# StaticPlatformMain_v1.net
KiCad netlist of a schematic drawn in EAGLE
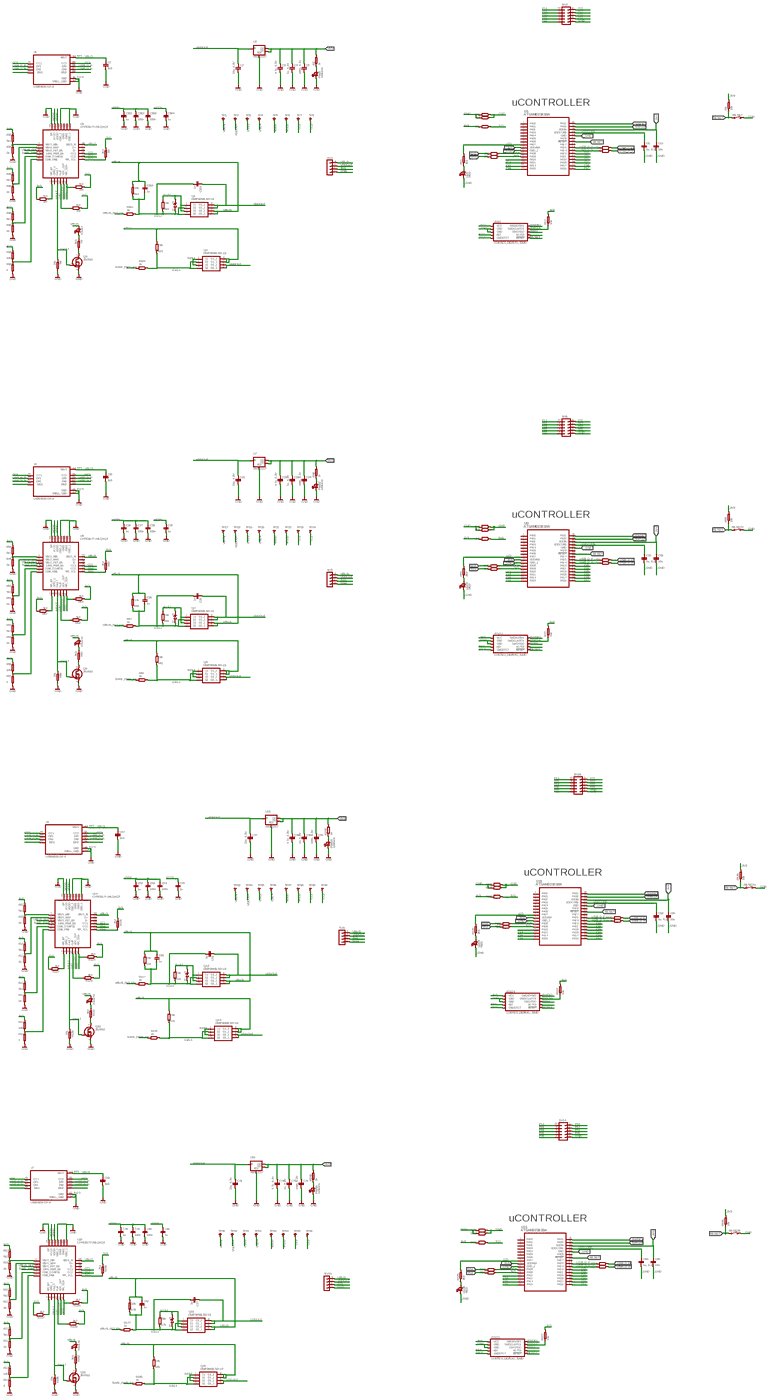
[diagram p0: schematic, sheet 1, overview]
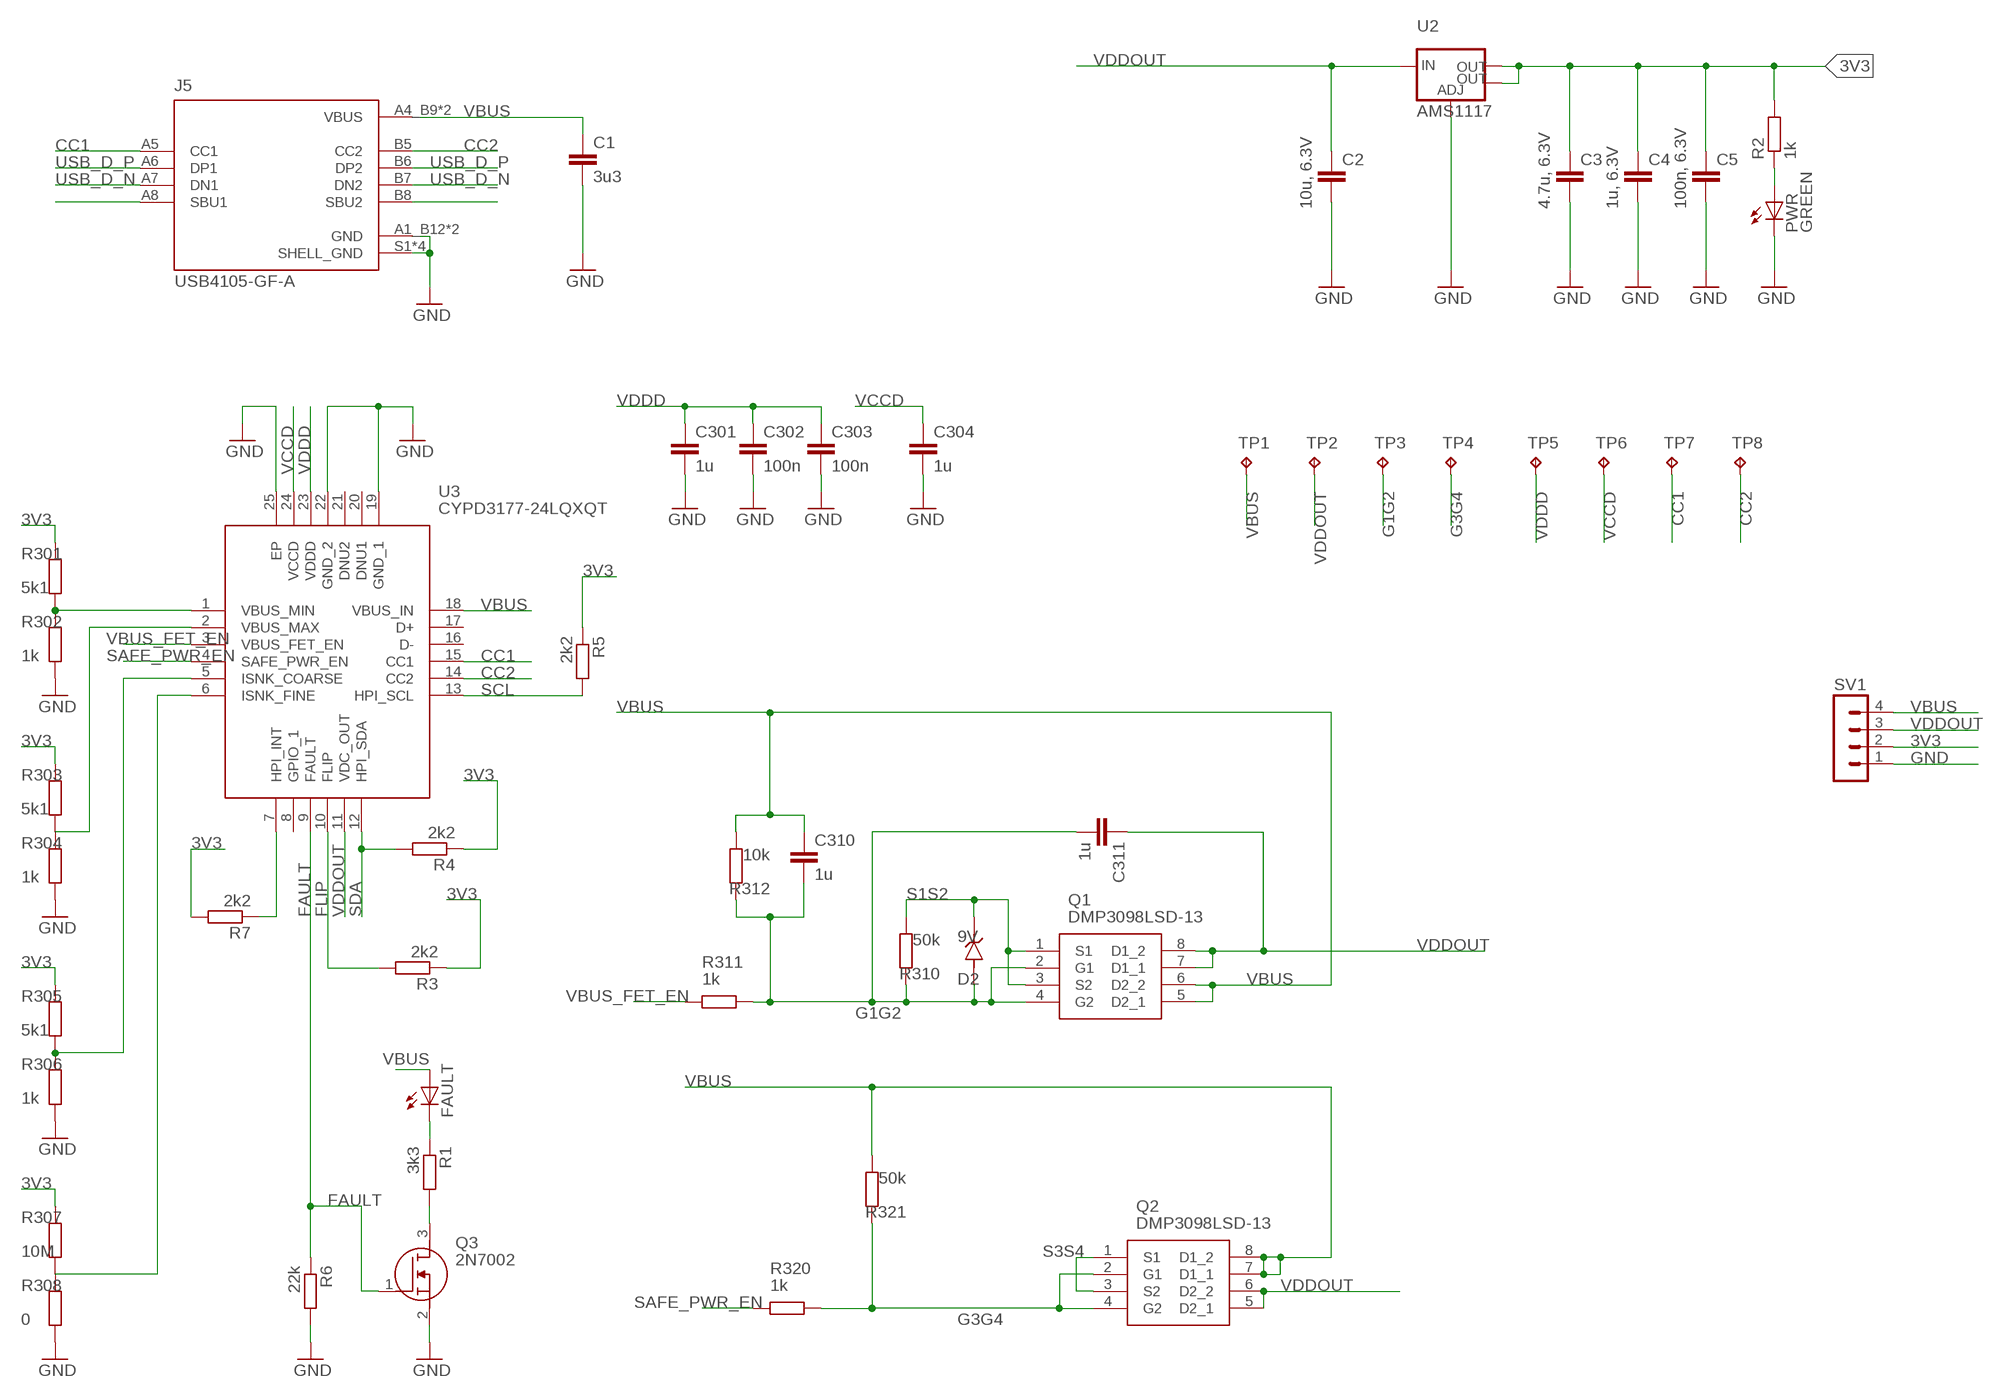
[diagram p1: schematic, sheet 1, part 1 of 6]
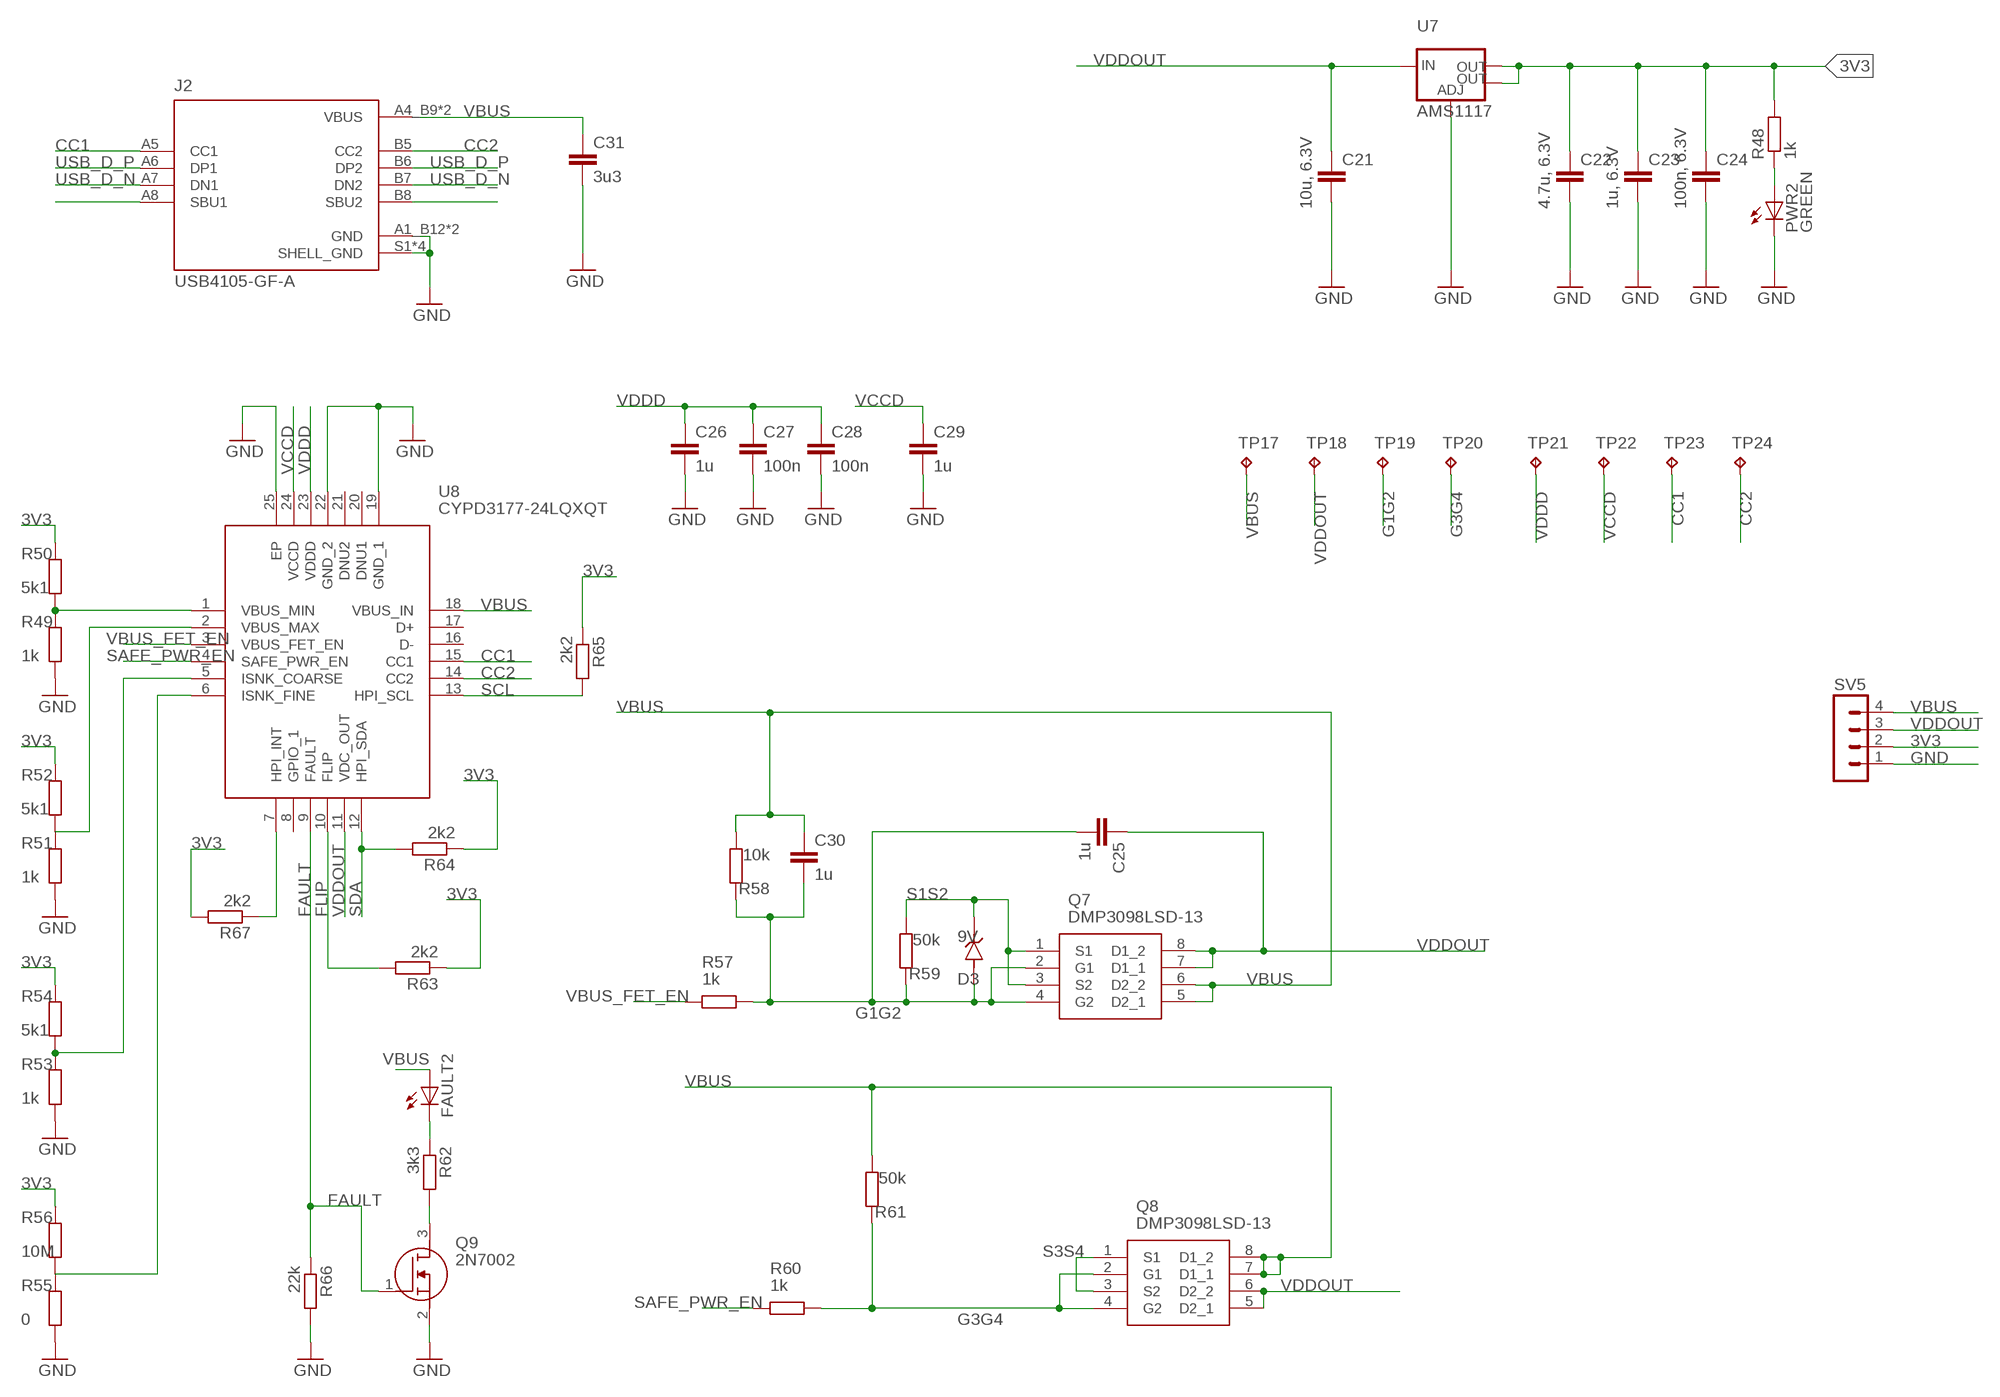
[diagram p2: schematic, sheet 1, part 2 of 6]
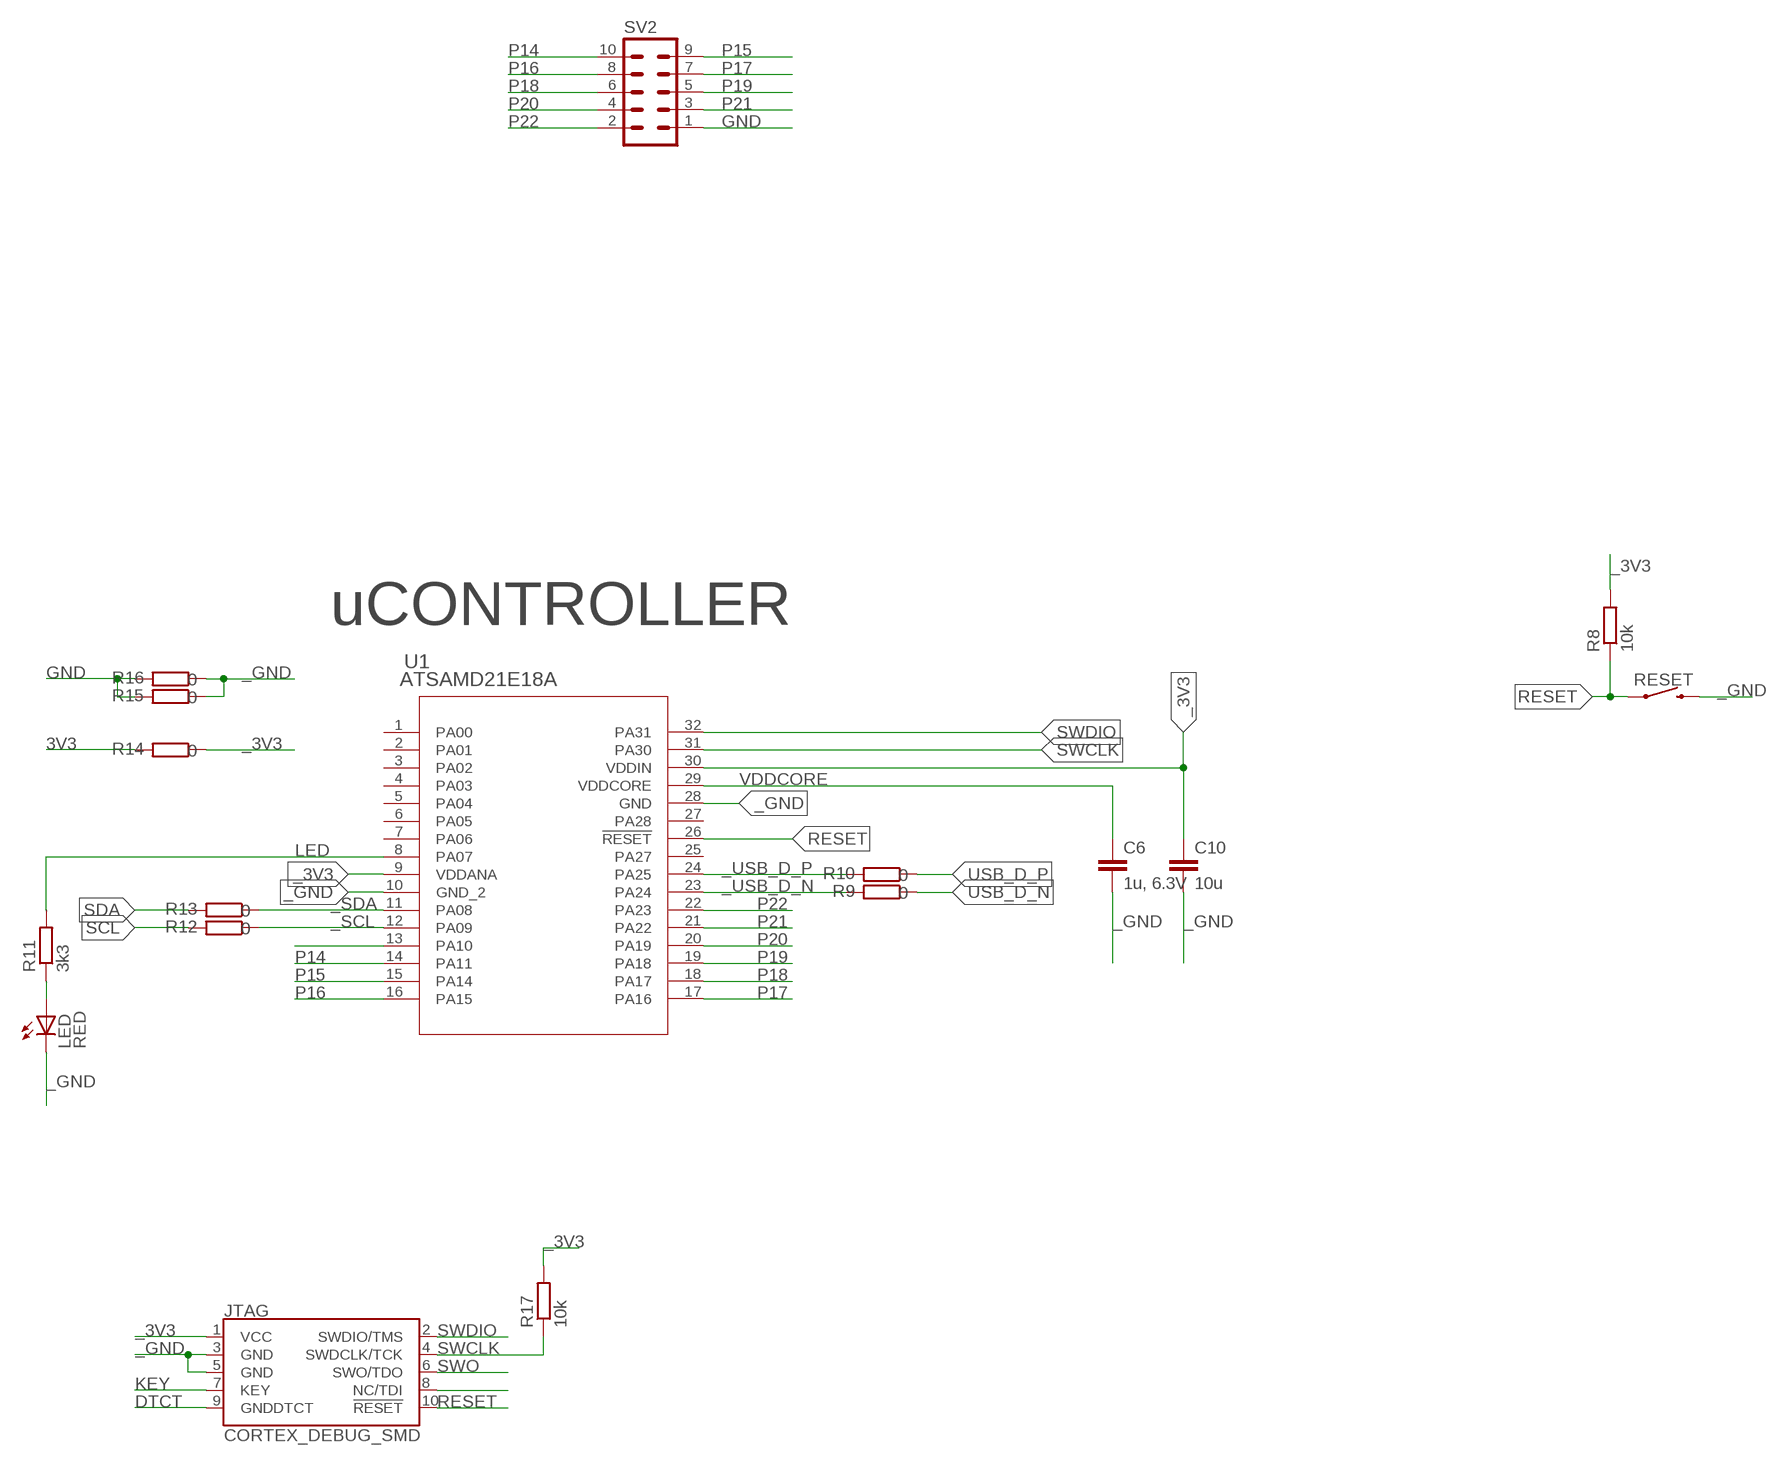
[diagram p3: schematic, sheet 1, part 3 of 6]
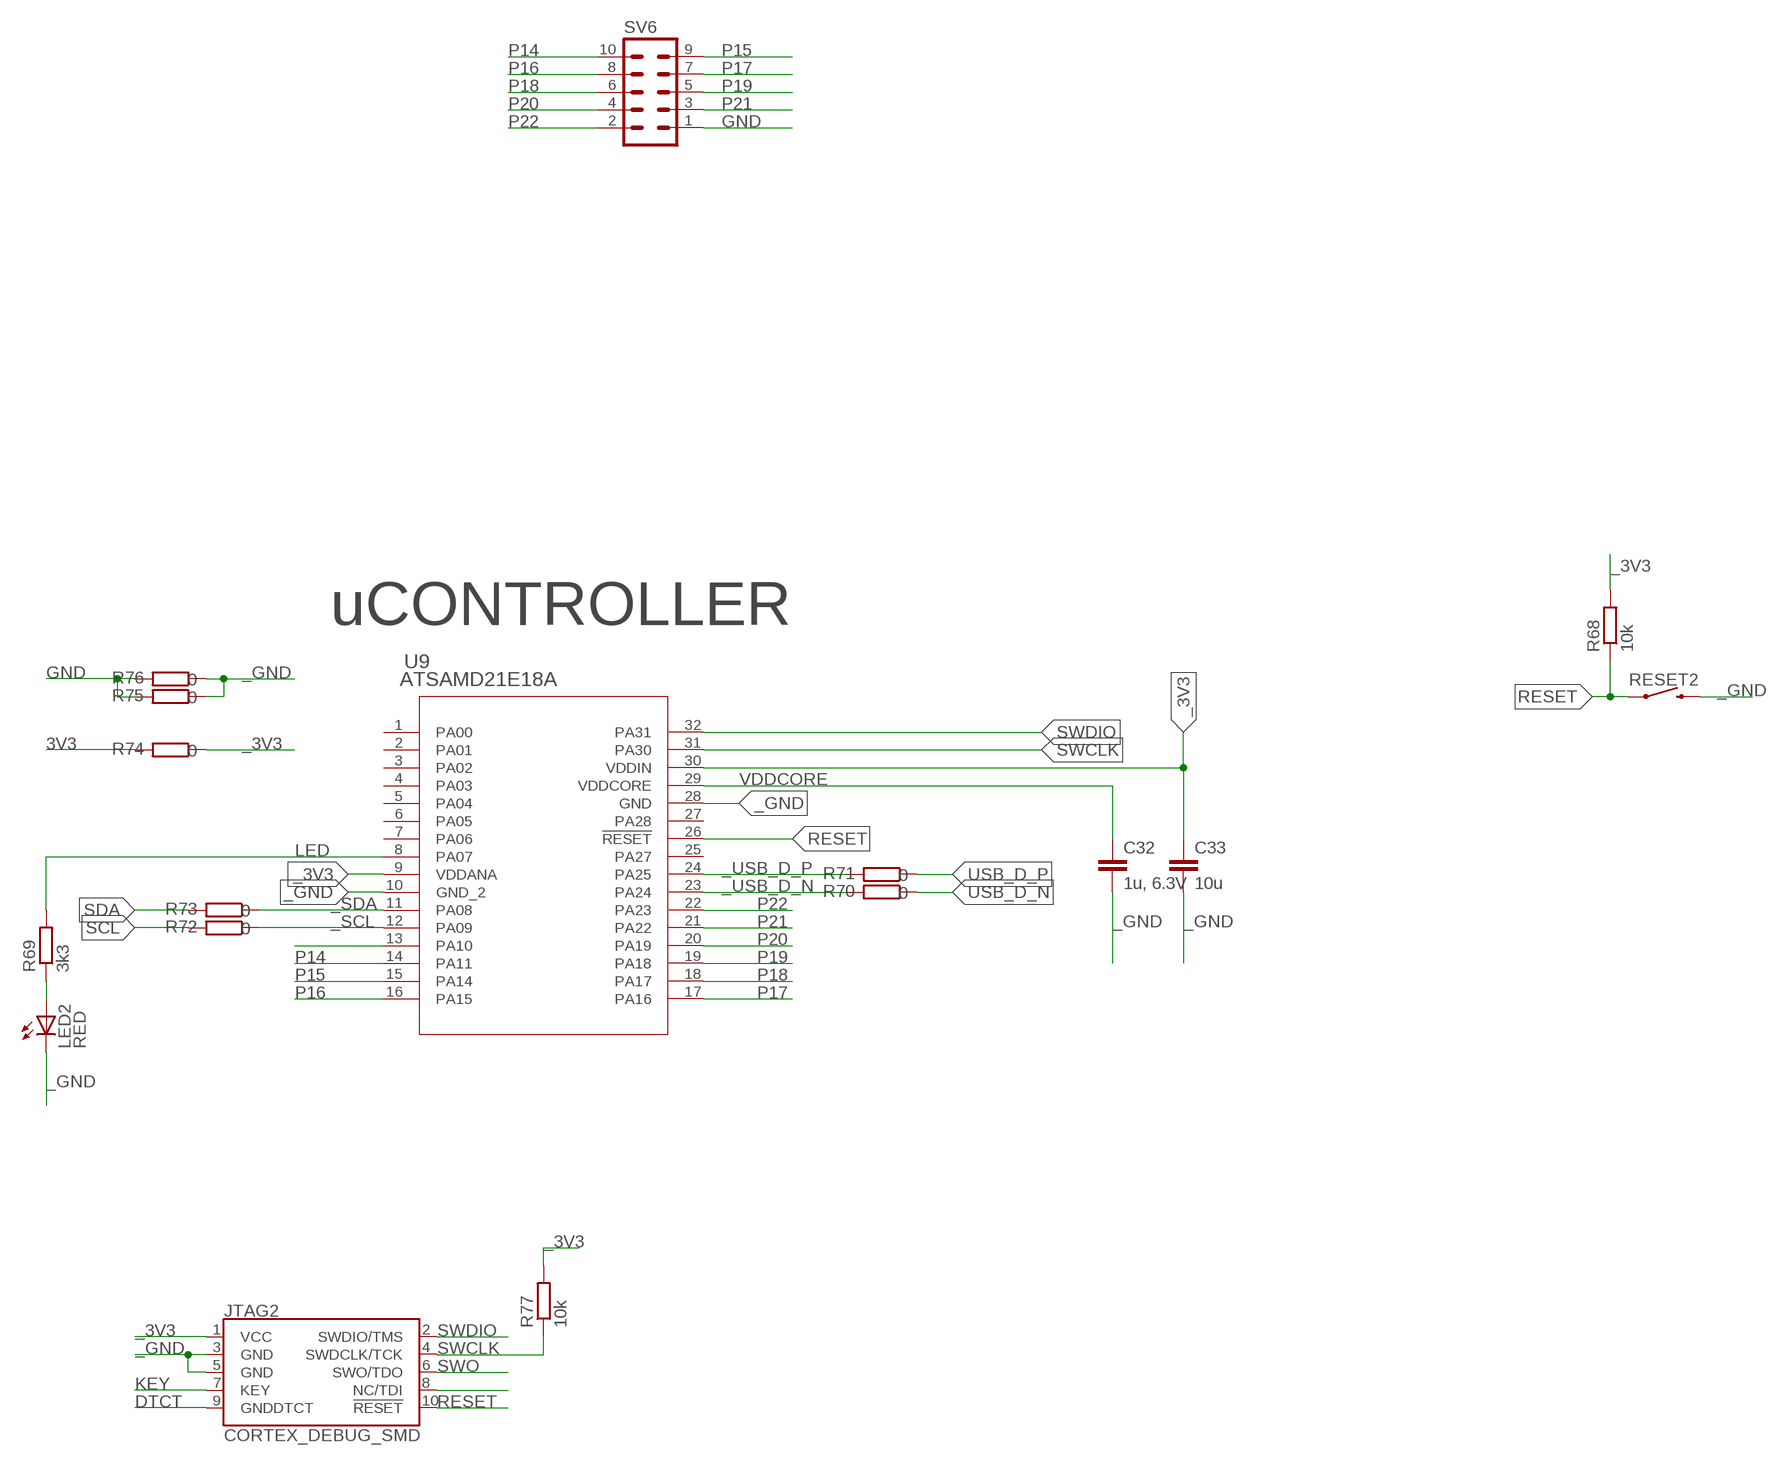
[diagram p4: schematic, sheet 1, part 4 of 6]
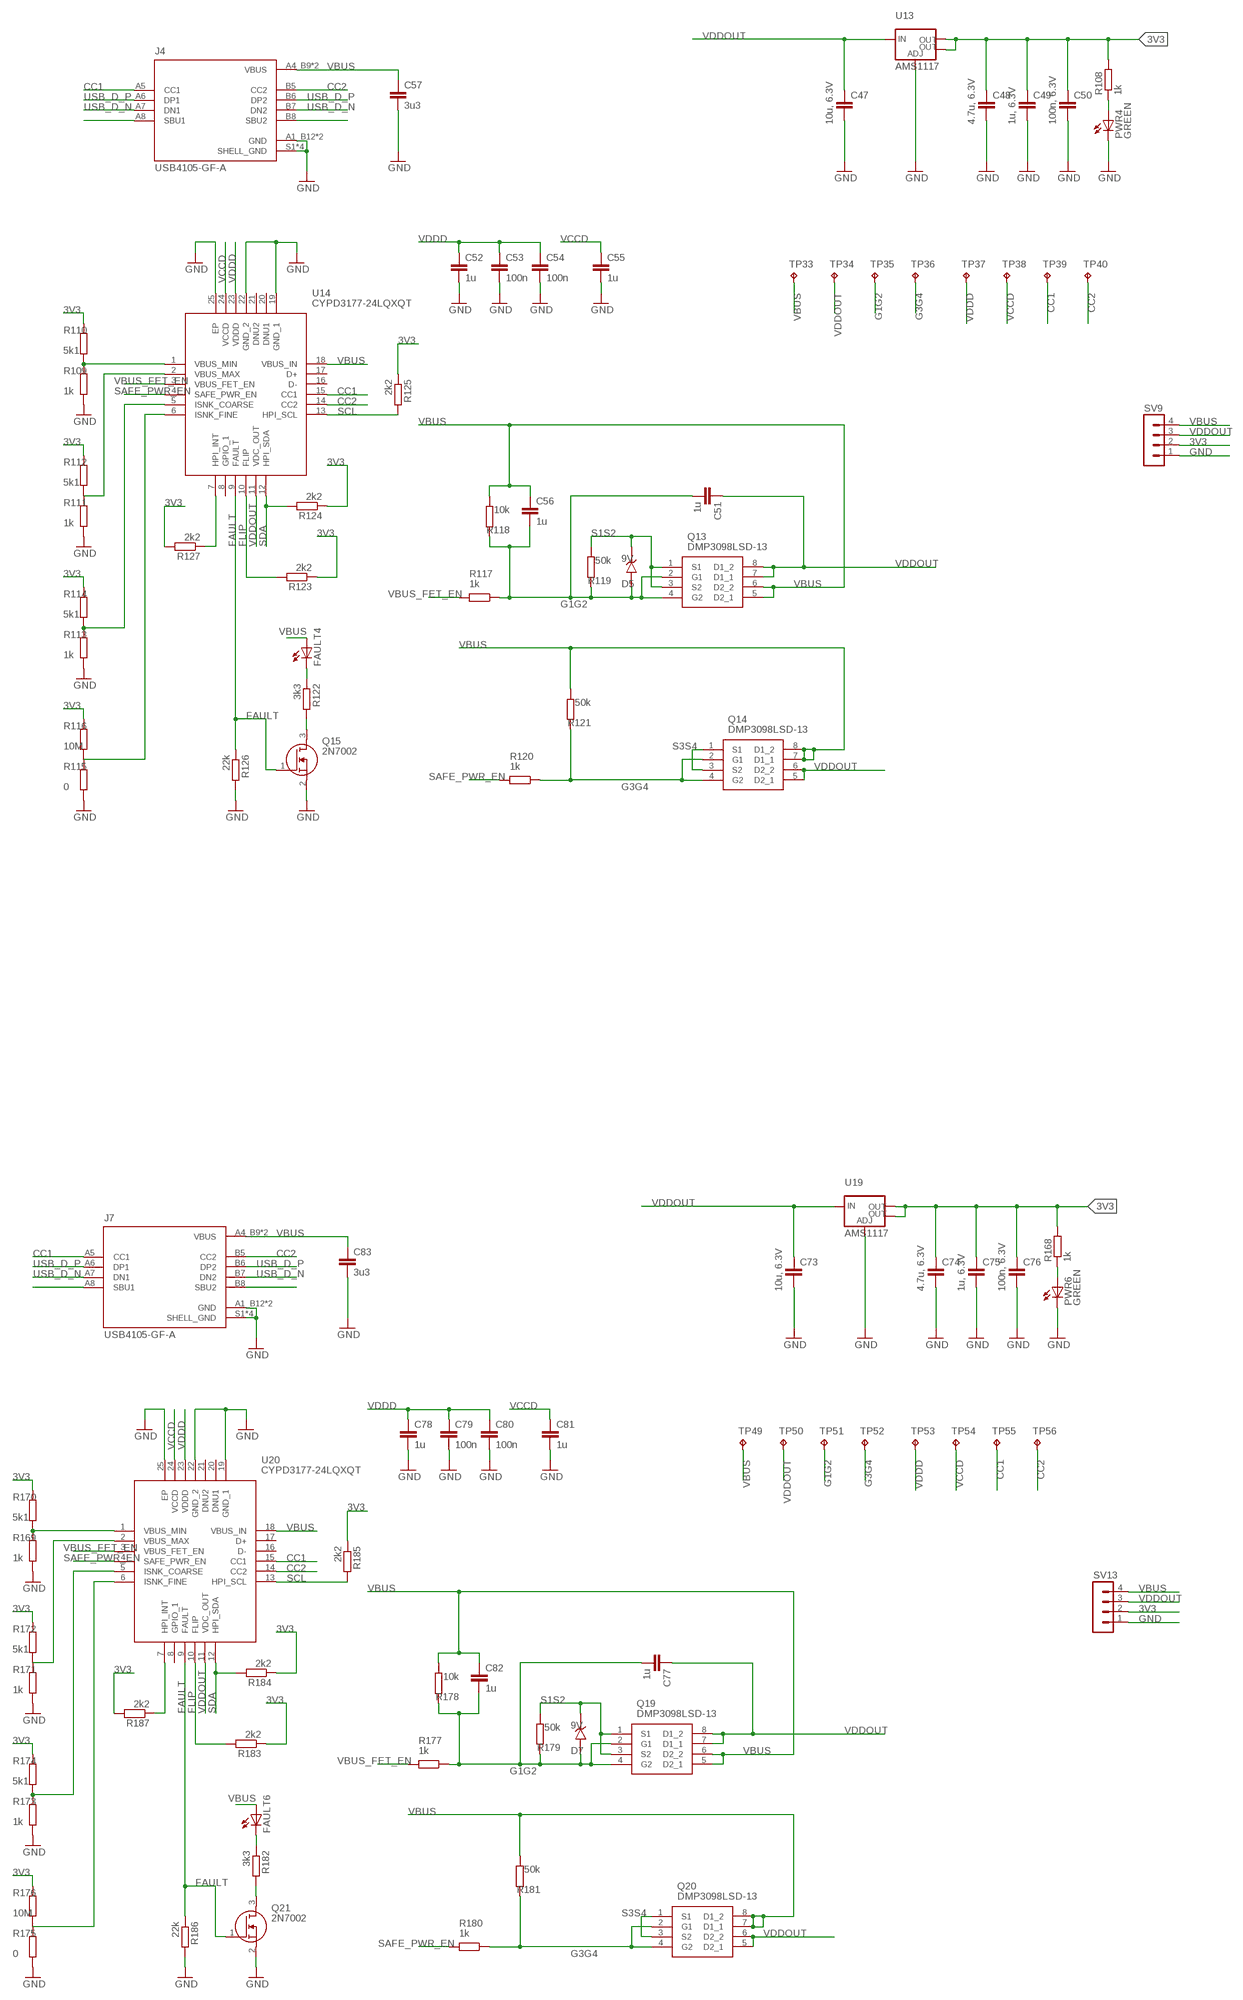
[diagram p5: schematic, sheet 1, part 5 of 6]
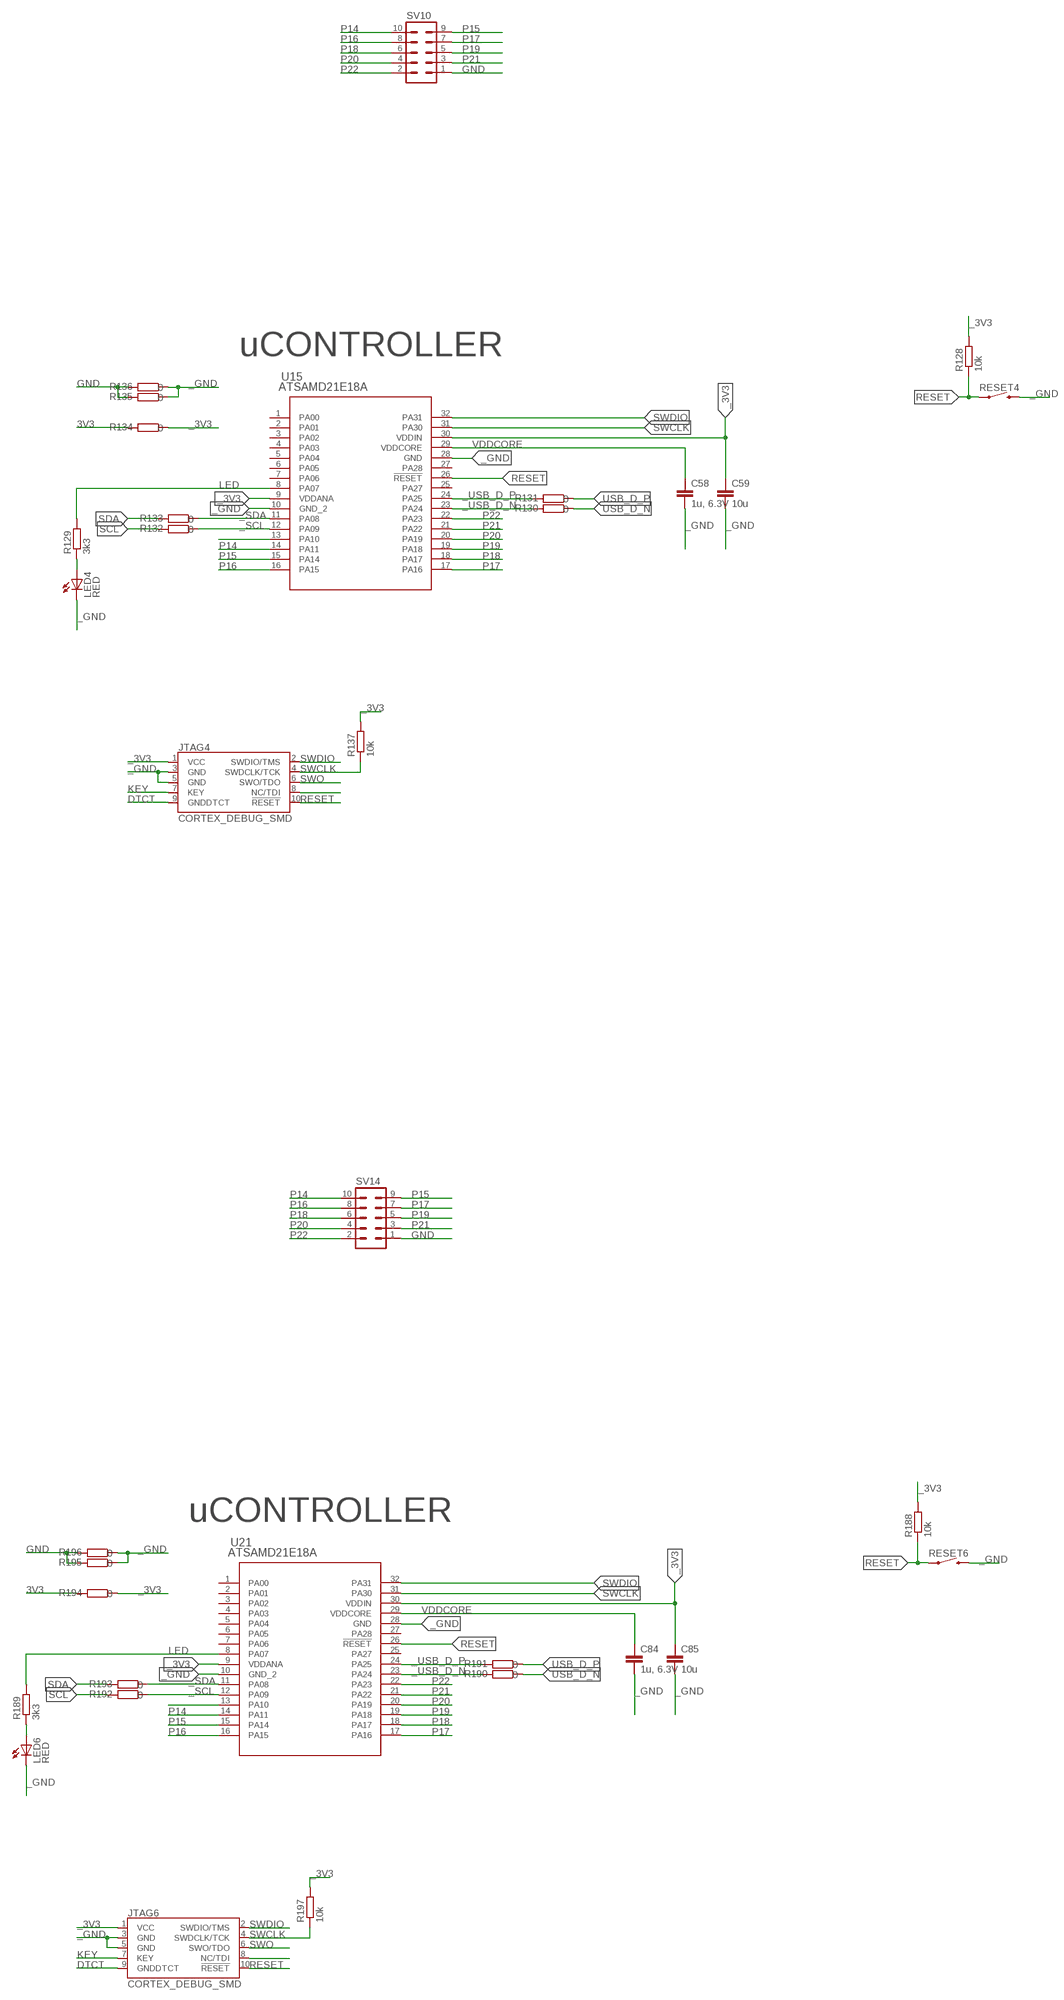
[diagram p6: schematic, sheet 1, part 6 of 6]

(export (version "E")
  (design (tool "Eeschema 10.0.6"))
  (components
    (comp (ref "C1")
      (value "3u3")
      (footprint "eagle-import:C0805K")
      (libsource (lib "eagle-import") (part "C-EUC0805K"))
    )
    (comp (ref "C2")
      (value "10u, 6.3V")
      (footprint "eagle-import:C0805K")
      (libsource (lib "eagle-import") (part "C-EUC0805K"))
    )
    (comp (ref "C3")
      (value "4.7u, 6.3V")
      (footprint "eagle-import:C0805K")
      (libsource (lib "eagle-import") (part "C-EUC0805K"))
    )
    (comp (ref "C4")
      (value "1u, 6.3V")
      (footprint "eagle-import:C0805K")
      (libsource (lib "eagle-import") (part "C-EUC0805K"))
    )
    (comp (ref "C5")
      (value "100n, 6.3V")
      (footprint "eagle-import:C0805K")
      (libsource (lib "eagle-import") (part "C-EUC0805K"))
    )
    (comp (ref "C6")
      (value "1u, 6.3V")
      (footprint "eagle-import:C0805")
      (libsource (lib "eagle-import") (part "C-EUC0805"))
    )
    (comp (ref "C10")
      (value "10u")
      (footprint "eagle-import:C0805")
      (libsource (lib "eagle-import") (part "C-EUC0805"))
    )
    (comp (ref "C21")
      (value "10u, 6.3V")
      (footprint "eagle-import:C0805K")
      (libsource (lib "eagle-import") (part "C-EUC0805K"))
    )
    (comp (ref "C22")
      (value "4.7u, 6.3V")
      (footprint "eagle-import:C0805K")
      (libsource (lib "eagle-import") (part "C-EUC0805K"))
    )
    (comp (ref "C23")
      (value "1u, 6.3V")
      (footprint "eagle-import:C0805K")
      (libsource (lib "eagle-import") (part "C-EUC0805K"))
    )
    (comp (ref "C24")
      (value "100n, 6.3V")
      (footprint "eagle-import:C0805K")
      (libsource (lib "eagle-import") (part "C-EUC0805K"))
    )
    (comp (ref "C25")
      (value "1u")
      (footprint "eagle-import:C0805K")
      (libsource (lib "eagle-import") (part "C-EUC0805K"))
    )
    (comp (ref "C26")
      (value "1u")
      (footprint "eagle-import:C0805K")
      (libsource (lib "eagle-import") (part "C-EUC0805K"))
    )
    (comp (ref "C27")
      (value "100n")
      (footprint "eagle-import:C0805K")
      (libsource (lib "eagle-import") (part "C-EUC0805K"))
    )
    (comp (ref "C28")
      (value "100n")
      (footprint "eagle-import:C0805K")
      (libsource (lib "eagle-import") (part "C-EUC0805K"))
    )
    (comp (ref "C29")
      (value "1u")
      (footprint "eagle-import:C0805K")
      (libsource (lib "eagle-import") (part "C-EUC0805K"))
    )
    (comp (ref "C30")
      (value "1u")
      (footprint "eagle-import:C0805K")
      (libsource (lib "eagle-import") (part "C-EUC0805K"))
    )
    (comp (ref "C31")
      (value "3u3")
      (footprint "eagle-import:C0805K")
      (libsource (lib "eagle-import") (part "C-EUC0805K"))
    )
    (comp (ref "C32")
      (value "1u, 6.3V")
      (footprint "eagle-import:C0805")
      (libsource (lib "eagle-import") (part "C-EUC0805"))
    )
    (comp (ref "C33")
      (value "10u")
      (footprint "eagle-import:C0805")
      (libsource (lib "eagle-import") (part "C-EUC0805"))
    )
    (comp (ref "C47")
      (value "10u, 6.3V")
      (footprint "eagle-import:C0805K")
      (libsource (lib "eagle-import") (part "C-EUC0805K"))
    )
    (comp (ref "C48")
      (value "4.7u, 6.3V")
      (footprint "eagle-import:C0805K")
      (libsource (lib "eagle-import") (part "C-EUC0805K"))
    )
    (comp (ref "C49")
      (value "1u, 6.3V")
      (footprint "eagle-import:C0805K")
      (libsource (lib "eagle-import") (part "C-EUC0805K"))
    )
    (comp (ref "C50")
      (value "100n, 6.3V")
      (footprint "eagle-import:C0805K")
      (libsource (lib "eagle-import") (part "C-EUC0805K"))
    )
    (comp (ref "C51")
      (value "1u")
      (footprint "eagle-import:C0805K")
      (libsource (lib "eagle-import") (part "C-EUC0805K"))
    )
    (comp (ref "C52")
      (value "1u")
      (footprint "eagle-import:C0805K")
      (libsource (lib "eagle-import") (part "C-EUC0805K"))
    )
    (comp (ref "C53")
      (value "100n")
      (footprint "eagle-import:C0805K")
      (libsource (lib "eagle-import") (part "C-EUC0805K"))
    )
    (comp (ref "C54")
      (value "100n")
      (footprint "eagle-import:C0805K")
      (libsource (lib "eagle-import") (part "C-EUC0805K"))
    )
    (comp (ref "C55")
      (value "1u")
      (footprint "eagle-import:C0805K")
      (libsource (lib "eagle-import") (part "C-EUC0805K"))
    )
    (comp (ref "C56")
      (value "1u")
      (footprint "eagle-import:C0805K")
      (libsource (lib "eagle-import") (part "C-EUC0805K"))
    )
    (comp (ref "C57")
      (value "3u3")
      (footprint "eagle-import:C0805K")
      (libsource (lib "eagle-import") (part "C-EUC0805K"))
    )
    (comp (ref "C58")
      (value "1u, 6.3V")
      (footprint "eagle-import:C0805")
      (libsource (lib "eagle-import") (part "C-EUC0805"))
    )
    (comp (ref "C59")
      (value "10u")
      (footprint "eagle-import:C0805")
      (libsource (lib "eagle-import") (part "C-EUC0805"))
    )
    (comp (ref "C73")
      (value "10u, 6.3V")
      (footprint "eagle-import:C0805K")
      (libsource (lib "eagle-import") (part "C-EUC0805K"))
    )
    (comp (ref "C74")
      (value "4.7u, 6.3V")
      (footprint "eagle-import:C0805K")
      (libsource (lib "eagle-import") (part "C-EUC0805K"))
    )
    (comp (ref "C75")
      (value "1u, 6.3V")
      (footprint "eagle-import:C0805K")
      (libsource (lib "eagle-import") (part "C-EUC0805K"))
    )
    (comp (ref "C76")
      (value "100n, 6.3V")
      (footprint "eagle-import:C0805K")
      (libsource (lib "eagle-import") (part "C-EUC0805K"))
    )
    (comp (ref "C77")
      (value "1u")
      (footprint "eagle-import:C0805K")
      (libsource (lib "eagle-import") (part "C-EUC0805K"))
    )
    (comp (ref "C78")
      (value "1u")
      (footprint "eagle-import:C0805K")
      (libsource (lib "eagle-import") (part "C-EUC0805K"))
    )
    (comp (ref "C79")
      (value "100n")
      (footprint "eagle-import:C0805K")
      (libsource (lib "eagle-import") (part "C-EUC0805K"))
    )
    (comp (ref "C80")
      (value "100n")
      (footprint "eagle-import:C0805K")
      (libsource (lib "eagle-import") (part "C-EUC0805K"))
    )
    (comp (ref "C81")
      (value "1u")
      (footprint "eagle-import:C0805K")
      (libsource (lib "eagle-import") (part "C-EUC0805K"))
    )
    (comp (ref "C82")
      (value "1u")
      (footprint "eagle-import:C0805K")
      (libsource (lib "eagle-import") (part "C-EUC0805K"))
    )
    (comp (ref "C83")
      (value "3u3")
      (footprint "eagle-import:C0805K")
      (libsource (lib "eagle-import") (part "C-EUC0805K"))
    )
    (comp (ref "C84")
      (value "1u, 6.3V")
      (footprint "eagle-import:C0805")
      (libsource (lib "eagle-import") (part "C-EUC0805"))
    )
    (comp (ref "C85")
      (value "10u")
      (footprint "eagle-import:C0805")
      (libsource (lib "eagle-import") (part "C-EUC0805"))
    )
    (comp (ref "C301")
      (value "1u")
      (footprint "eagle-import:C0805K")
      (libsource (lib "eagle-import") (part "C-EUC0805K"))
    )
    (comp (ref "C302")
      (value "100n")
      (footprint "eagle-import:C0805K")
      (libsource (lib "eagle-import") (part "C-EUC0805K"))
    )
    (comp (ref "C303")
      (value "100n")
      (footprint "eagle-import:C0805K")
      (libsource (lib "eagle-import") (part "C-EUC0805K"))
    )
    (comp (ref "C304")
      (value "1u")
      (footprint "eagle-import:C0805K")
      (libsource (lib "eagle-import") (part "C-EUC0805K"))
    )
    (comp (ref "C310")
      (value "1u")
      (footprint "eagle-import:C0805K")
      (libsource (lib "eagle-import") (part "C-EUC0805K"))
    )
    (comp (ref "C311")
      (value "1u")
      (footprint "eagle-import:C0805K")
      (libsource (lib "eagle-import") (part "C-EUC0805K"))
    )
    (comp (ref "D2")
      (value "9V")
      (footprint "eagle-import:DIOMELF3515N")
      (fields (field (name "MF") "Taiwan Semiconductor Corporation") (field (name "MP") "BZV55C12 L0G"))
      (libsource (lib "eagle-import") (part "BZV55C12_L0G"))
    )
    (comp (ref "D3")
      (value "9V")
      (footprint "eagle-import:DIOMELF3515N")
      (fields (field (name "MF") "Taiwan Semiconductor Corporation") (field (name "MP") "BZV55C12 L0G"))
      (libsource (lib "eagle-import") (part "BZV55C12_L0G"))
    )
    (comp (ref "D5")
      (value "9V")
      (footprint "eagle-import:DIOMELF3515N")
      (fields (field (name "MF") "Taiwan Semiconductor Corporation") (field (name "MP") "BZV55C12 L0G"))
      (libsource (lib "eagle-import") (part "BZV55C12_L0G"))
    )
    (comp (ref "D7")
      (value "9V")
      (footprint "eagle-import:DIOMELF3515N")
      (fields (field (name "MF") "Taiwan Semiconductor Corporation") (field (name "MP") "BZV55C12 L0G"))
      (libsource (lib "eagle-import") (part "BZV55C12_L0G"))
    )
    (comp (ref "FAULT")
      (value "GREEN")
      (footprint "eagle-import:CHIPLED_0805")
      (libsource (lib "eagle-import") (part "LEDCHIPLED_0805"))
    )
    (comp (ref "FAULT2")
      (value "GREEN")
      (footprint "eagle-import:CHIPLED_0805")
      (libsource (lib "eagle-import") (part "LEDCHIPLED_0805"))
    )
    (comp (ref "FAULT4")
      (value "GREEN")
      (footprint "eagle-import:CHIPLED_0805")
      (libsource (lib "eagle-import") (part "LEDCHIPLED_0805"))
    )
    (comp (ref "FAULT6")
      (value "GREEN")
      (footprint "eagle-import:CHIPLED_0805")
      (libsource (lib "eagle-import") (part "LEDCHIPLED_0805"))
    )
    (comp (ref "J2")
      (value "USB4105-GF-A")
      (footprint "eagle-import:GCT_USB4105-GF-A")
      (fields (field (name "MF") "GCT"))
      (libsource (lib "eagle-import") (part "USB4105-GF-A"))
    )
    (comp (ref "J4")
      (value "USB4105-GF-A")
      (footprint "eagle-import:GCT_USB4105-GF-A")
      (fields (field (name "MF") "GCT"))
      (libsource (lib "eagle-import") (part "USB4105-GF-A"))
    )
    (comp (ref "J5")
      (value "USB4105-GF-A")
      (footprint "eagle-import:GCT_USB4105-GF-A")
      (fields (field (name "MF") "GCT"))
      (libsource (lib "eagle-import") (part "USB4105-GF-A"))
    )
    (comp (ref "J7")
      (value "USB4105-GF-A")
      (footprint "eagle-import:GCT_USB4105-GF-A")
      (fields (field (name "MF") "GCT"))
      (libsource (lib "eagle-import") (part "USB4105-GF-A"))
    )
    (comp (ref "JTAG")
      (value "CORTEX_DEBUG_SMD")
      (footprint "eagle-import:SAMTECH_FTSH-105-01")
      (libsource (lib "eagle-import") (part "CORTEX_DEBUG_SMD"))
    )
    (comp (ref "JTAG2")
      (value "CORTEX_DEBUG_SMD")
      (footprint "eagle-import:SAMTECH_FTSH-105-01")
      (libsource (lib "eagle-import") (part "CORTEX_DEBUG_SMD"))
    )
    (comp (ref "JTAG4")
      (value "CORTEX_DEBUG_SMD")
      (footprint "eagle-import:SAMTECH_FTSH-105-01")
      (libsource (lib "eagle-import") (part "CORTEX_DEBUG_SMD"))
    )
    (comp (ref "JTAG6")
      (value "CORTEX_DEBUG_SMD")
      (footprint "eagle-import:SAMTECH_FTSH-105-01")
      (libsource (lib "eagle-import") (part "CORTEX_DEBUG_SMD"))
    )
    (comp (ref "LED")
      (value "RED")
      (footprint "eagle-import:CHIPLED_0805")
      (libsource (lib "eagle-import") (part "LEDCHIPLED_0805"))
    )
    (comp (ref "LED2")
      (value "RED")
      (footprint "eagle-import:CHIPLED_0805")
      (libsource (lib "eagle-import") (part "LEDCHIPLED_0805"))
    )
    (comp (ref "LED4")
      (value "RED")
      (footprint "eagle-import:CHIPLED_0805")
      (libsource (lib "eagle-import") (part "LEDCHIPLED_0805"))
    )
    (comp (ref "LED6")
      (value "RED")
      (footprint "eagle-import:CHIPLED_0805")
      (libsource (lib "eagle-import") (part "LEDCHIPLED_0805"))
    )
    (comp (ref "PWR")
      (value "GREEN")
      (footprint "eagle-import:CHIPLED_0805")
      (libsource (lib "eagle-import") (part "LEDCHIPLED_0805"))
    )
    (comp (ref "PWR2")
      (value "GREEN")
      (footprint "eagle-import:CHIPLED_0805")
      (libsource (lib "eagle-import") (part "LEDCHIPLED_0805"))
    )
    (comp (ref "PWR4")
      (value "GREEN")
      (footprint "eagle-import:CHIPLED_0805")
      (libsource (lib "eagle-import") (part "LEDCHIPLED_0805"))
    )
    (comp (ref "PWR6")
      (value "GREEN")
      (footprint "eagle-import:CHIPLED_0805")
      (libsource (lib "eagle-import") (part "LEDCHIPLED_0805"))
    )
    (comp (ref "Q1")
      (value "DMP3098LSD-13")
      (footprint "eagle-import:SOIC127P600X175-8N")
      (fields (field (name "MOUSER_PART_NUMBER") "621-DMP3098LSD-13"))
      (libsource (lib "eagle-import") (part "DMP3098LSD-13"))
    )
    (comp (ref "Q2")
      (value "DMP3098LSD-13")
      (footprint "eagle-import:SOIC127P600X175-8N")
      (fields (field (name "MOUSER_PART_NUMBER") "621-DMP3098LSD-13"))
      (libsource (lib "eagle-import") (part "DMP3098LSD-13"))
    )
    (comp (ref "Q3")
      (value "2N7002")
      (footprint "eagle-import:SOT96P240X120-3N")
      (fields (field (name "MOUSER_PART_NUMBER") "512-2N7002"))
      (libsource (lib "eagle-import") (part "2N7002"))
    )
    (comp (ref "Q7")
      (value "DMP3098LSD-13")
      (footprint "eagle-import:SOIC127P600X175-8N")
      (fields (field (name "MOUSER_PART_NUMBER") "621-DMP3098LSD-13"))
      (libsource (lib "eagle-import") (part "DMP3098LSD-13"))
    )
    (comp (ref "Q8")
      (value "DMP3098LSD-13")
      (footprint "eagle-import:SOIC127P600X175-8N")
      (fields (field (name "MOUSER_PART_NUMBER") "621-DMP3098LSD-13"))
      (libsource (lib "eagle-import") (part "DMP3098LSD-13"))
    )
    (comp (ref "Q9")
      (value "2N7002")
      (footprint "eagle-import:SOT96P240X120-3N")
      (fields (field (name "MOUSER_PART_NUMBER") "512-2N7002"))
      (libsource (lib "eagle-import") (part "2N7002"))
    )
    (comp (ref "Q13")
      (value "DMP3098LSD-13")
      (footprint "eagle-import:SOIC127P600X175-8N")
      (fields (field (name "MOUSER_PART_NUMBER") "621-DMP3098LSD-13"))
      (libsource (lib "eagle-import") (part "DMP3098LSD-13"))
    )
    (comp (ref "Q14")
      (value "DMP3098LSD-13")
      (footprint "eagle-import:SOIC127P600X175-8N")
      (fields (field (name "MOUSER_PART_NUMBER") "621-DMP3098LSD-13"))
      (libsource (lib "eagle-import") (part "DMP3098LSD-13"))
    )
    (comp (ref "Q15")
      (value "2N7002")
      (footprint "eagle-import:SOT96P240X120-3N")
      (fields (field (name "MOUSER_PART_NUMBER") "512-2N7002"))
      (libsource (lib "eagle-import") (part "2N7002"))
    )
    (comp (ref "Q19")
      (value "DMP3098LSD-13")
      (footprint "eagle-import:SOIC127P600X175-8N")
      (fields (field (name "MOUSER_PART_NUMBER") "621-DMP3098LSD-13"))
      (libsource (lib "eagle-import") (part "DMP3098LSD-13"))
    )
    (comp (ref "Q20")
      (value "DMP3098LSD-13")
      (footprint "eagle-import:SOIC127P600X175-8N")
      (fields (field (name "MOUSER_PART_NUMBER") "621-DMP3098LSD-13"))
      (libsource (lib "eagle-import") (part "DMP3098LSD-13"))
    )
    (comp (ref "Q21")
      (value "2N7002")
      (footprint "eagle-import:SOT96P240X120-3N")
      (fields (field (name "MOUSER_PART_NUMBER") "512-2N7002"))
      (libsource (lib "eagle-import") (part "2N7002"))
    )
    (comp (ref "R1")
      (value "3k3")
      (footprint "eagle-import:R0805")
      (libsource (lib "eagle-import") (part "R-EU_R0805"))
    )
    (comp (ref "R2")
      (value "1k")
      (footprint "eagle-import:R0805")
      (libsource (lib "eagle-import") (part "R-EU_R0805"))
    )
    (comp (ref "R3")
      (value "2k2")
      (footprint "eagle-import:R0805")
      (libsource (lib "eagle-import") (part "R-EU_R0805"))
    )
    (comp (ref "R4")
      (value "2k2")
      (footprint "eagle-import:R0805")
      (libsource (lib "eagle-import") (part "R-EU_R0805"))
    )
    (comp (ref "R5")
      (value "2k2")
      (footprint "eagle-import:R0805")
      (libsource (lib "eagle-import") (part "R-EU_R0805"))
    )
    (comp (ref "R6")
      (value "22k")
      (footprint "eagle-import:R0805")
      (libsource (lib "eagle-import") (part "R-EU_R0805"))
    )
    (comp (ref "R7")
      (value "2k2")
      (footprint "eagle-import:R0805")
      (libsource (lib "eagle-import") (part "R-EU_R0805"))
    )
    (comp (ref "R8")
      (value "10k")
      (footprint "eagle-import:R0805")
      (libsource (lib "eagle-import") (part "R-EU_R0805"))
    )
    (comp (ref "R9")
      (value "0")
      (footprint "eagle-import:R0805")
      (libsource (lib "eagle-import") (part "R-EU_R0805"))
    )
    (comp (ref "R10")
      (value "0")
      (footprint "eagle-import:R0805")
      (libsource (lib "eagle-import") (part "R-EU_R0805"))
    )
    (comp (ref "R11")
      (value "3k3")
      (footprint "eagle-import:R0805")
      (libsource (lib "eagle-import") (part "R-EU_R0805"))
    )
    (comp (ref "R12")
      (value "0")
      (footprint "eagle-import:R0805")
      (libsource (lib "eagle-import") (part "R-EU_R0805"))
    )
    (comp (ref "R13")
      (value "0")
      (footprint "eagle-import:R0805")
      (libsource (lib "eagle-import") (part "R-EU_R0805"))
    )
    (comp (ref "R14")
      (value "0")
      (footprint "eagle-import:R0805")
      (libsource (lib "eagle-import") (part "R-EU_R0805"))
    )
    (comp (ref "R15")
      (value "0")
      (footprint "eagle-import:R0805")
      (libsource (lib "eagle-import") (part "R-EU_R0805"))
    )
    (comp (ref "R16")
      (value "0")
      (footprint "eagle-import:R0805")
      (libsource (lib "eagle-import") (part "R-EU_R0805"))
    )
    (comp (ref "R17")
      (value "10k")
      (footprint "eagle-import:R0805")
      (libsource (lib "eagle-import") (part "R-EU_R0805"))
    )
    (comp (ref "R48")
      (value "1k")
      (footprint "eagle-import:R0805")
      (libsource (lib "eagle-import") (part "R-EU_R0805"))
    )
    (comp (ref "R49")
      (value "1k")
      (footprint "eagle-import:R0805")
      (libsource (lib "eagle-import") (part "R-EU_R0805"))
    )
    (comp (ref "R50")
      (value "5k1")
      (footprint "eagle-import:R0805")
      (libsource (lib "eagle-import") (part "R-EU_R0805"))
    )
    (comp (ref "R51")
      (value "1k")
      (footprint "eagle-import:R0805")
      (libsource (lib "eagle-import") (part "R-EU_R0805"))
    )
    (comp (ref "R52")
      (value "5k1")
      (footprint "eagle-import:R0805")
      (libsource (lib "eagle-import") (part "R-EU_R0805"))
    )
    (comp (ref "R53")
      (value "1k")
      (footprint "eagle-import:R0805")
      (libsource (lib "eagle-import") (part "R-EU_R0805"))
    )
    (comp (ref "R54")
      (value "5k1")
      (footprint "eagle-import:R0805")
      (libsource (lib "eagle-import") (part "R-EU_R0805"))
    )
    (comp (ref "R55")
      (value "0")
      (footprint "eagle-import:R0805")
      (libsource (lib "eagle-import") (part "R-EU_R0805"))
    )
    (comp (ref "R56")
      (value "10M")
      (footprint "eagle-import:R0805")
      (libsource (lib "eagle-import") (part "R-EU_R0805"))
    )
    (comp (ref "R57")
      (value "1k")
      (footprint "eagle-import:R0805")
      (libsource (lib "eagle-import") (part "R-EU_R0805"))
    )
    (comp (ref "R58")
      (value "10k")
      (footprint "eagle-import:R0805")
      (libsource (lib "eagle-import") (part "R-EU_R0805"))
    )
    (comp (ref "R59")
      (value "50k")
      (footprint "eagle-import:R0805")
      (libsource (lib "eagle-import") (part "R-EU_R0805"))
    )
    (comp (ref "R60")
      (value "1k")
      (footprint "eagle-import:R0805")
      (libsource (lib "eagle-import") (part "R-EU_R0805"))
    )
    (comp (ref "R61")
      (value "50k")
      (footprint "eagle-import:R0805")
      (libsource (lib "eagle-import") (part "R-EU_R0805"))
    )
    (comp (ref "R62")
      (value "3k3")
      (footprint "eagle-import:R0805")
      (libsource (lib "eagle-import") (part "R-EU_R0805"))
    )
    (comp (ref "R63")
      (value "2k2")
      (footprint "eagle-import:R0805")
      (libsource (lib "eagle-import") (part "R-EU_R0805"))
    )
    (comp (ref "R64")
      (value "2k2")
      (footprint "eagle-import:R0805")
      (libsource (lib "eagle-import") (part "R-EU_R0805"))
    )
    (comp (ref "R65")
      (value "2k2")
      (footprint "eagle-import:R0805")
      (libsource (lib "eagle-import") (part "R-EU_R0805"))
    )
    (comp (ref "R66")
      (value "22k")
      (footprint "eagle-import:R0805")
      (libsource (lib "eagle-import") (part "R-EU_R0805"))
    )
    (comp (ref "R67")
      (value "2k2")
      (footprint "eagle-import:R0805")
      (libsource (lib "eagle-import") (part "R-EU_R0805"))
    )
    (comp (ref "R68")
      (value "10k")
      (footprint "eagle-import:R0805")
      (libsource (lib "eagle-import") (part "R-EU_R0805"))
    )
    (comp (ref "R69")
      (value "3k3")
      (footprint "eagle-import:R0805")
      (libsource (lib "eagle-import") (part "R-EU_R0805"))
    )
    (comp (ref "R70")
      (value "0")
      (footprint "eagle-import:R0805")
      (libsource (lib "eagle-import") (part "R-EU_R0805"))
    )
    (comp (ref "R71")
      (value "0")
      (footprint "eagle-import:R0805")
      (libsource (lib "eagle-import") (part "R-EU_R0805"))
    )
    (comp (ref "R72")
      (value "0")
      (footprint "eagle-import:R0805")
      (libsource (lib "eagle-import") (part "R-EU_R0805"))
    )
    (comp (ref "R73")
      (value "0")
      (footprint "eagle-import:R0805")
      (libsource (lib "eagle-import") (part "R-EU_R0805"))
    )
    (comp (ref "R74")
      (value "0")
      (footprint "eagle-import:R0805")
      (libsource (lib "eagle-import") (part "R-EU_R0805"))
    )
    (comp (ref "R75")
      (value "0")
      (footprint "eagle-import:R0805")
      (libsource (lib "eagle-import") (part "R-EU_R0805"))
    )
    (comp (ref "R76")
      (value "0")
      (footprint "eagle-import:R0805")
      (libsource (lib "eagle-import") (part "R-EU_R0805"))
    )
    (comp (ref "R77")
      (value "10k")
      (footprint "eagle-import:R0805")
      (libsource (lib "eagle-import") (part "R-EU_R0805"))
    )
    (comp (ref "R108")
      (value "1k")
      (footprint "eagle-import:R0805")
      (libsource (lib "eagle-import") (part "R-EU_R0805"))
    )
    (comp (ref "R109")
      (value "1k")
      (footprint "eagle-import:R0805")
      (libsource (lib "eagle-import") (part "R-EU_R0805"))
    )
    (comp (ref "R110")
      (value "5k1")
      (footprint "eagle-import:R0805")
      (libsource (lib "eagle-import") (part "R-EU_R0805"))
    )
    (comp (ref "R111")
      (value "1k")
      (footprint "eagle-import:R0805")
      (libsource (lib "eagle-import") (part "R-EU_R0805"))
    )
    (comp (ref "R112")
      (value "5k1")
      (footprint "eagle-import:R0805")
      (libsource (lib "eagle-import") (part "R-EU_R0805"))
    )
    (comp (ref "R113")
      (value "1k")
      (footprint "eagle-import:R0805")
      (libsource (lib "eagle-import") (part "R-EU_R0805"))
    )
    (comp (ref "R114")
      (value "5k1")
      (footprint "eagle-import:R0805")
      (libsource (lib "eagle-import") (part "R-EU_R0805"))
    )
    (comp (ref "R115")
      (value "0")
      (footprint "eagle-import:R0805")
      (libsource (lib "eagle-import") (part "R-EU_R0805"))
    )
    (comp (ref "R116")
      (value "10M")
      (footprint "eagle-import:R0805")
      (libsource (lib "eagle-import") (part "R-EU_R0805"))
    )
    (comp (ref "R117")
      (value "1k")
      (footprint "eagle-import:R0805")
      (libsource (lib "eagle-import") (part "R-EU_R0805"))
    )
    (comp (ref "R118")
      (value "10k")
      (footprint "eagle-import:R0805")
      (libsource (lib "eagle-import") (part "R-EU_R0805"))
    )
    (comp (ref "R119")
      (value "50k")
      (footprint "eagle-import:R0805")
      (libsource (lib "eagle-import") (part "R-EU_R0805"))
    )
    (comp (ref "R120")
      (value "1k")
      (footprint "eagle-import:R0805")
      (libsource (lib "eagle-import") (part "R-EU_R0805"))
    )
    (comp (ref "R121")
      (value "50k")
      (footprint "eagle-import:R0805")
      (libsource (lib "eagle-import") (part "R-EU_R0805"))
    )
    (comp (ref "R122")
      (value "3k3")
      (footprint "eagle-import:R0805")
      (libsource (lib "eagle-import") (part "R-EU_R0805"))
    )
    (comp (ref "R123")
      (value "2k2")
      (footprint "eagle-import:R0805")
      (libsource (lib "eagle-import") (part "R-EU_R0805"))
    )
    (comp (ref "R124")
      (value "2k2")
      (footprint "eagle-import:R0805")
      (libsource (lib "eagle-import") (part "R-EU_R0805"))
    )
    (comp (ref "R125")
      (value "2k2")
      (footprint "eagle-import:R0805")
      (libsource (lib "eagle-import") (part "R-EU_R0805"))
    )
    (comp (ref "R126")
      (value "22k")
      (footprint "eagle-import:R0805")
      (libsource (lib "eagle-import") (part "R-EU_R0805"))
    )
    (comp (ref "R127")
      (value "2k2")
      (footprint "eagle-import:R0805")
      (libsource (lib "eagle-import") (part "R-EU_R0805"))
    )
    (comp (ref "R128")
      (value "10k")
      (footprint "eagle-import:R0805")
      (libsource (lib "eagle-import") (part "R-EU_R0805"))
    )
    (comp (ref "R129")
      (value "3k3")
      (footprint "eagle-import:R0805")
      (libsource (lib "eagle-import") (part "R-EU_R0805"))
    )
    (comp (ref "R130")
      (value "0")
      (footprint "eagle-import:R0805")
      (libsource (lib "eagle-import") (part "R-EU_R0805"))
    )
    (comp (ref "R131")
      (value "0")
      (footprint "eagle-import:R0805")
      (libsource (lib "eagle-import") (part "R-EU_R0805"))
    )
    (comp (ref "R132")
      (value "0")
      (footprint "eagle-import:R0805")
      (libsource (lib "eagle-import") (part "R-EU_R0805"))
    )
    (comp (ref "R133")
      (value "0")
      (footprint "eagle-import:R0805")
      (libsource (lib "eagle-import") (part "R-EU_R0805"))
    )
    (comp (ref "R134")
      (value "0")
      (footprint "eagle-import:R0805")
      (libsource (lib "eagle-import") (part "R-EU_R0805"))
    )
    (comp (ref "R135")
      (value "0")
      (footprint "eagle-import:R0805")
      (libsource (lib "eagle-import") (part "R-EU_R0805"))
    )
    (comp (ref "R136")
      (value "0")
      (footprint "eagle-import:R0805")
      (libsource (lib "eagle-import") (part "R-EU_R0805"))
    )
    (comp (ref "R137")
      (value "10k")
      (footprint "eagle-import:R0805")
      (libsource (lib "eagle-import") (part "R-EU_R0805"))
    )
    (comp (ref "R168")
      (value "1k")
      (footprint "eagle-import:R0805")
      (libsource (lib "eagle-import") (part "R-EU_R0805"))
    )
    (comp (ref "R169")
      (value "1k")
      (footprint "eagle-import:R0805")
      (libsource (lib "eagle-import") (part "R-EU_R0805"))
    )
    (comp (ref "R170")
      (value "5k1")
      (footprint "eagle-import:R0805")
      (libsource (lib "eagle-import") (part "R-EU_R0805"))
    )
    (comp (ref "R171")
      (value "1k")
      (footprint "eagle-import:R0805")
      (libsource (lib "eagle-import") (part "R-EU_R0805"))
    )
    (comp (ref "R172")
      (value "5k1")
      (footprint "eagle-import:R0805")
      (libsource (lib "eagle-import") (part "R-EU_R0805"))
    )
    (comp (ref "R173")
      (value "1k")
      (footprint "eagle-import:R0805")
      (libsource (lib "eagle-import") (part "R-EU_R0805"))
    )
    (comp (ref "R174")
      (value "5k1")
      (footprint "eagle-import:R0805")
      (libsource (lib "eagle-import") (part "R-EU_R0805"))
    )
    (comp (ref "R175")
      (value "0")
      (footprint "eagle-import:R0805")
      (libsource (lib "eagle-import") (part "R-EU_R0805"))
    )
    (comp (ref "R176")
      (value "10M")
      (footprint "eagle-import:R0805")
      (libsource (lib "eagle-import") (part "R-EU_R0805"))
    )
    (comp (ref "R177")
      (value "1k")
      (footprint "eagle-import:R0805")
      (libsource (lib "eagle-import") (part "R-EU_R0805"))
    )
    (comp (ref "R178")
      (value "10k")
      (footprint "eagle-import:R0805")
      (libsource (lib "eagle-import") (part "R-EU_R0805"))
    )
    (comp (ref "R179")
      (value "50k")
      (footprint "eagle-import:R0805")
      (libsource (lib "eagle-import") (part "R-EU_R0805"))
    )
    (comp (ref "R180")
      (value "1k")
      (footprint "eagle-import:R0805")
      (libsource (lib "eagle-import") (part "R-EU_R0805"))
    )
    (comp (ref "R181")
      (value "50k")
      (footprint "eagle-import:R0805")
      (libsource (lib "eagle-import") (part "R-EU_R0805"))
    )
    (comp (ref "R182")
      (value "3k3")
      (footprint "eagle-import:R0805")
      (libsource (lib "eagle-import") (part "R-EU_R0805"))
    )
    (comp (ref "R183")
      (value "2k2")
      (footprint "eagle-import:R0805")
      (libsource (lib "eagle-import") (part "R-EU_R0805"))
    )
    (comp (ref "R184")
      (value "2k2")
      (footprint "eagle-import:R0805")
      (libsource (lib "eagle-import") (part "R-EU_R0805"))
    )
    (comp (ref "R185")
      (value "2k2")
      (footprint "eagle-import:R0805")
      (libsource (lib "eagle-import") (part "R-EU_R0805"))
    )
    (comp (ref "R186")
      (value "22k")
      (footprint "eagle-import:R0805")
      (libsource (lib "eagle-import") (part "R-EU_R0805"))
    )
    (comp (ref "R187")
      (value "2k2")
      (footprint "eagle-import:R0805")
      (libsource (lib "eagle-import") (part "R-EU_R0805"))
    )
    (comp (ref "R188")
      (value "10k")
      (footprint "eagle-import:R0805")
      (libsource (lib "eagle-import") (part "R-EU_R0805"))
    )
    (comp (ref "R189")
      (value "3k3")
      (footprint "eagle-import:R0805")
      (libsource (lib "eagle-import") (part "R-EU_R0805"))
    )
    (comp (ref "R190")
      (value "0")
      (footprint "eagle-import:R0805")
      (libsource (lib "eagle-import") (part "R-EU_R0805"))
    )
    (comp (ref "R191")
      (value "0")
      (footprint "eagle-import:R0805")
      (libsource (lib "eagle-import") (part "R-EU_R0805"))
    )
    (comp (ref "R192")
      (value "0")
      (footprint "eagle-import:R0805")
      (libsource (lib "eagle-import") (part "R-EU_R0805"))
    )
    (comp (ref "R193")
      (value "0")
      (footprint "eagle-import:R0805")
      (libsource (lib "eagle-import") (part "R-EU_R0805"))
    )
    (comp (ref "R194")
      (value "0")
      (footprint "eagle-import:R0805")
      (libsource (lib "eagle-import") (part "R-EU_R0805"))
    )
    (comp (ref "R195")
      (value "0")
      (footprint "eagle-import:R0805")
      (libsource (lib "eagle-import") (part "R-EU_R0805"))
    )
    (comp (ref "R196")
      (value "0")
      (footprint "eagle-import:R0805")
      (libsource (lib "eagle-import") (part "R-EU_R0805"))
    )
    (comp (ref "R197")
      (value "10k")
      (footprint "eagle-import:R0805")
      (libsource (lib "eagle-import") (part "R-EU_R0805"))
    )
    (comp (ref "R301")
      (value "5k1")
      (footprint "eagle-import:R0805")
      (libsource (lib "eagle-import") (part "R-EU_R0805"))
    )
    (comp (ref "R302")
      (value "1k")
      (footprint "eagle-import:R0805")
      (libsource (lib "eagle-import") (part "R-EU_R0805"))
    )
    (comp (ref "R303")
      (value "5k1")
      (footprint "eagle-import:R0805")
      (libsource (lib "eagle-import") (part "R-EU_R0805"))
    )
    (comp (ref "R304")
      (value "1k")
      (footprint "eagle-import:R0805")
      (libsource (lib "eagle-import") (part "R-EU_R0805"))
    )
    (comp (ref "R305")
      (value "5k1")
      (footprint "eagle-import:R0805")
      (libsource (lib "eagle-import") (part "R-EU_R0805"))
    )
    (comp (ref "R306")
      (value "1k")
      (footprint "eagle-import:R0805")
      (libsource (lib "eagle-import") (part "R-EU_R0805"))
    )
    (comp (ref "R307")
      (value "10M")
      (footprint "eagle-import:R0805")
      (libsource (lib "eagle-import") (part "R-EU_R0805"))
    )
    (comp (ref "R308")
      (value "0")
      (footprint "eagle-import:R0805")
      (libsource (lib "eagle-import") (part "R-EU_R0805"))
    )
    (comp (ref "R310")
      (value "50k")
      (footprint "eagle-import:R0805")
      (libsource (lib "eagle-import") (part "R-EU_R0805"))
    )
    (comp (ref "R311")
      (value "1k")
      (footprint "eagle-import:R0805")
      (libsource (lib "eagle-import") (part "R-EU_R0805"))
    )
    (comp (ref "R312")
      (value "10k")
      (footprint "eagle-import:R0805")
      (libsource (lib "eagle-import") (part "R-EU_R0805"))
    )
    (comp (ref "R320")
      (value "1k")
      (footprint "eagle-import:R0805")
      (libsource (lib "eagle-import") (part "R-EU_R0805"))
    )
    (comp (ref "R321")
      (value "50k")
      (footprint "eagle-import:R0805")
      (libsource (lib "eagle-import") (part "R-EU_R0805"))
    )
    (comp (ref "RESET")
      (value "MOMENTARY-SWITCH-SPST-SMD-6.0X3.5MM")
      (footprint "eagle-import:TACTILE_SWITCH_SMD_6.0X3.5MM")
      (libsource (lib "eagle-import") (part "MOMENTARY-SWITCH-SPST-SMD-6.0X3.5MM"))
    )
    (comp (ref "RESET2")
      (value "MOMENTARY-SWITCH-SPST-SMD-6.0X3.5MM")
      (footprint "eagle-import:TACTILE_SWITCH_SMD_6.0X3.5MM")
      (libsource (lib "eagle-import") (part "MOMENTARY-SWITCH-SPST-SMD-6.0X3.5MM"))
    )
    (comp (ref "RESET4")
      (value "MOMENTARY-SWITCH-SPST-SMD-6.0X3.5MM")
      (footprint "eagle-import:TACTILE_SWITCH_SMD_6.0X3.5MM")
      (libsource (lib "eagle-import") (part "MOMENTARY-SWITCH-SPST-SMD-6.0X3.5MM"))
    )
    (comp (ref "RESET6")
      (value "MOMENTARY-SWITCH-SPST-SMD-6.0X3.5MM")
      (footprint "eagle-import:TACTILE_SWITCH_SMD_6.0X3.5MM")
      (libsource (lib "eagle-import") (part "MOMENTARY-SWITCH-SPST-SMD-6.0X3.5MM"))
    )
    (comp (ref "SV1")
      (value "MA04-1")
      (footprint "eagle-import:MA04-1")
      (libsource (lib "eagle-import") (part "MA04-1"))
    )
    (comp (ref "SV2")
      (value "MA05-2")
      (footprint "eagle-import:MA05-2")
      (libsource (lib "eagle-import") (part "MA05-2"))
    )
    (comp (ref "SV5")
      (value "MA04-1")
      (footprint "eagle-import:MA04-1")
      (libsource (lib "eagle-import") (part "MA04-1"))
    )
    (comp (ref "SV6")
      (value "MA05-2")
      (footprint "eagle-import:MA05-2")
      (libsource (lib "eagle-import") (part "MA05-2"))
    )
    (comp (ref "SV9")
      (value "MA04-1")
      (footprint "eagle-import:MA04-1")
      (libsource (lib "eagle-import") (part "MA04-1"))
    )
    (comp (ref "SV10")
      (value "MA05-2")
      (footprint "eagle-import:MA05-2")
      (libsource (lib "eagle-import") (part "MA05-2"))
    )
    (comp (ref "SV13")
      (value "MA04-1")
      (footprint "eagle-import:MA04-1")
      (libsource (lib "eagle-import") (part "MA04-1"))
    )
    (comp (ref "SV14")
      (value "MA05-2")
      (footprint "eagle-import:MA05-2")
      (libsource (lib "eagle-import") (part "MA05-2"))
    )
    (comp (ref "TP1")
      (value "TPTP18R")
      (footprint "eagle-import:TP18R")
      (libsource (lib "eagle-import") (part "TPTP18R"))
    )
    (comp (ref "TP2")
      (value "TPTP18R")
      (footprint "eagle-import:TP18R")
      (libsource (lib "eagle-import") (part "TPTP18R"))
    )
    (comp (ref "TP3")
      (value "TPTP18R")
      (footprint "eagle-import:TP18R")
      (libsource (lib "eagle-import") (part "TPTP18R"))
    )
    (comp (ref "TP4")
      (value "TPTP18R")
      (footprint "eagle-import:TP18R")
      (libsource (lib "eagle-import") (part "TPTP18R"))
    )
    (comp (ref "TP5")
      (value "TPTP18R")
      (footprint "eagle-import:TP18R")
      (libsource (lib "eagle-import") (part "TPTP18R"))
    )
    (comp (ref "TP6")
      (value "TPTP18R")
      (footprint "eagle-import:TP18R")
      (libsource (lib "eagle-import") (part "TPTP18R"))
    )
    (comp (ref "TP7")
      (value "TPTP18R")
      (footprint "eagle-import:TP18R")
      (libsource (lib "eagle-import") (part "TPTP18R"))
    )
    (comp (ref "TP8")
      (value "TPTP18R")
      (footprint "eagle-import:TP18R")
      (libsource (lib "eagle-import") (part "TPTP18R"))
    )
    (comp (ref "TP17")
      (value "TPTP18R")
      (footprint "eagle-import:TP18R")
      (libsource (lib "eagle-import") (part "TPTP18R"))
    )
    (comp (ref "TP18")
      (value "TPTP18R")
      (footprint "eagle-import:TP18R")
      (libsource (lib "eagle-import") (part "TPTP18R"))
    )
    (comp (ref "TP19")
      (value "TPTP18R")
      (footprint "eagle-import:TP18R")
      (libsource (lib "eagle-import") (part "TPTP18R"))
    )
    (comp (ref "TP20")
      (value "TPTP18R")
      (footprint "eagle-import:TP18R")
      (libsource (lib "eagle-import") (part "TPTP18R"))
    )
    (comp (ref "TP21")
      (value "TPTP18R")
      (footprint "eagle-import:TP18R")
      (libsource (lib "eagle-import") (part "TPTP18R"))
    )
    (comp (ref "TP22")
      (value "TPTP18R")
      (footprint "eagle-import:TP18R")
      (libsource (lib "eagle-import") (part "TPTP18R"))
    )
    (comp (ref "TP23")
      (value "TPTP18R")
      (footprint "eagle-import:TP18R")
      (libsource (lib "eagle-import") (part "TPTP18R"))
    )
    (comp (ref "TP24")
      (value "TPTP18R")
      (footprint "eagle-import:TP18R")
      (libsource (lib "eagle-import") (part "TPTP18R"))
    )
    (comp (ref "TP33")
      (value "TPTP18R")
      (footprint "eagle-import:TP18R")
      (libsource (lib "eagle-import") (part "TPTP18R"))
    )
    (comp (ref "TP34")
      (value "TPTP18R")
      (footprint "eagle-import:TP18R")
      (libsource (lib "eagle-import") (part "TPTP18R"))
    )
    (comp (ref "TP35")
      (value "TPTP18R")
      (footprint "eagle-import:TP18R")
      (libsource (lib "eagle-import") (part "TPTP18R"))
    )
    (comp (ref "TP36")
      (value "TPTP18R")
      (footprint "eagle-import:TP18R")
      (libsource (lib "eagle-import") (part "TPTP18R"))
    )
    (comp (ref "TP37")
      (value "TPTP18R")
      (footprint "eagle-import:TP18R")
      (libsource (lib "eagle-import") (part "TPTP18R"))
    )
    (comp (ref "TP38")
      (value "TPTP18R")
      (footprint "eagle-import:TP18R")
      (libsource (lib "eagle-import") (part "TPTP18R"))
    )
    (comp (ref "TP39")
      (value "TPTP18R")
      (footprint "eagle-import:TP18R")
      (libsource (lib "eagle-import") (part "TPTP18R"))
    )
    (comp (ref "TP40")
      (value "TPTP18R")
      (footprint "eagle-import:TP18R")
      (libsource (lib "eagle-import") (part "TPTP18R"))
    )
    (comp (ref "TP49")
      (value "TPTP18R")
      (footprint "eagle-import:TP18R")
      (libsource (lib "eagle-import") (part "TPTP18R"))
    )
    (comp (ref "TP50")
      (value "TPTP18R")
      (footprint "eagle-import:TP18R")
      (libsource (lib "eagle-import") (part "TPTP18R"))
    )
    (comp (ref "TP51")
      (value "TPTP18R")
      (footprint "eagle-import:TP18R")
      (libsource (lib "eagle-import") (part "TPTP18R"))
    )
    (comp (ref "TP52")
      (value "TPTP18R")
      (footprint "eagle-import:TP18R")
      (libsource (lib "eagle-import") (part "TPTP18R"))
    )
    (comp (ref "TP53")
      (value "TPTP18R")
      (footprint "eagle-import:TP18R")
      (libsource (lib "eagle-import") (part "TPTP18R"))
    )
    (comp (ref "TP54")
      (value "TPTP18R")
      (footprint "eagle-import:TP18R")
      (libsource (lib "eagle-import") (part "TPTP18R"))
    )
    (comp (ref "TP55")
      (value "TPTP18R")
      (footprint "eagle-import:TP18R")
      (libsource (lib "eagle-import") (part "TPTP18R"))
    )
    (comp (ref "TP56")
      (value "TPTP18R")
      (footprint "eagle-import:TP18R")
      (libsource (lib "eagle-import") (part "TPTP18R"))
    )
    (comp (ref "U1")
      (value "ATSAMD21E18A")
      (footprint "eagle-import:TQFP32_MC_MCH-M")
      (fields
        (field (name "MANUFACTURER_PART_NUMBER") "ATSAMD21E18A-AU")
        (field (name "COPYRIGHT") "Copyright (C) 2022 Ultra Librarian. All rights reserved.")
      )
      (libsource (lib "eagle-import") (part "ATSAMD21E18A-AUTQFP32_MC_MCH-M"))
    )
    (comp (ref "U2")
      (value "AMS1117")
      (footprint "eagle-import:SOT223")
      (libsource (lib "eagle-import") (part "V_REG_LM1117SOT223"))
    )
    (comp (ref "U3")
      (value "CYPD3177-24LQXQT")
      (footprint "eagle-import:QFN50P400X400X60-25N")
      (fields (field (name "MOUSER_PART_NUMBER") "727-CYPD3177-24LQXQT"))
      (libsource (lib "eagle-import") (part "CYPD3177-24LQXQT"))
    )
    (comp (ref "U7")
      (value "AMS1117")
      (footprint "eagle-import:SOT223")
      (libsource (lib "eagle-import") (part "V_REG_LM1117SOT223"))
    )
    (comp (ref "U8")
      (value "CYPD3177-24LQXQT")
      (footprint "eagle-import:QFN50P400X400X60-25N")
      (fields (field (name "MOUSER_PART_NUMBER") "727-CYPD3177-24LQXQT"))
      (libsource (lib "eagle-import") (part "CYPD3177-24LQXQT"))
    )
    (comp (ref "U9")
      (value "ATSAMD21E18A")
      (footprint "eagle-import:TQFP32_MC_MCH-M")
      (fields
        (field (name "MANUFACTURER_PART_NUMBER") "ATSAMD21E18A-AU")
        (field (name "COPYRIGHT") "Copyright (C) 2022 Ultra Librarian. All rights reserved.")
      )
      (libsource (lib "eagle-import") (part "ATSAMD21E18A-AUTQFP32_MC_MCH-M"))
    )
    (comp (ref "U13")
      (value "AMS1117")
      (footprint "eagle-import:SOT223")
      (libsource (lib "eagle-import") (part "V_REG_LM1117SOT223"))
    )
    (comp (ref "U14")
      (value "CYPD3177-24LQXQT")
      (footprint "eagle-import:QFN50P400X400X60-25N")
      (fields (field (name "MOUSER_PART_NUMBER") "727-CYPD3177-24LQXQT"))
      (libsource (lib "eagle-import") (part "CYPD3177-24LQXQT"))
    )
    (comp (ref "U15")
      (value "ATSAMD21E18A")
      (footprint "eagle-import:TQFP32_MC_MCH-M")
      (fields
        (field (name "MANUFACTURER_PART_NUMBER") "ATSAMD21E18A-AU")
        (field (name "COPYRIGHT") "Copyright (C) 2022 Ultra Librarian. All rights reserved.")
      )
      (libsource (lib "eagle-import") (part "ATSAMD21E18A-AUTQFP32_MC_MCH-M"))
    )
    (comp (ref "U19")
      (value "AMS1117")
      (footprint "eagle-import:SOT223")
      (libsource (lib "eagle-import") (part "V_REG_LM1117SOT223"))
    )
    (comp (ref "U20")
      (value "CYPD3177-24LQXQT")
      (footprint "eagle-import:QFN50P400X400X60-25N")
      (fields (field (name "MOUSER_PART_NUMBER") "727-CYPD3177-24LQXQT"))
      (libsource (lib "eagle-import") (part "CYPD3177-24LQXQT"))
    )
    (comp (ref "U21")
      (value "ATSAMD21E18A")
      (footprint "eagle-import:TQFP32_MC_MCH-M")
      (fields
        (field (name "MANUFACTURER_PART_NUMBER") "ATSAMD21E18A-AU")
        (field (name "COPYRIGHT") "Copyright (C) 2022 Ultra Librarian. All rights reserved.")
      )
      (libsource (lib "eagle-import") (part "ATSAMD21E18A-AUTQFP32_MC_MCH-M"))
    )
  )
  (nets
    (net (code "1") (name "/CC1") (class "Default")
      (node (ref "J2") (pin "A5") (pinfunction "CC1_A5") (pintype "bidirectional"))
      (node (ref "J4") (pin "A5") (pinfunction "CC1_A5") (pintype "bidirectional"))
      (node (ref "J5") (pin "A5") (pinfunction "CC1_A5") (pintype "bidirectional"))
      (node (ref "J7") (pin "A5") (pinfunction "CC1_A5") (pintype "bidirectional"))
      (node (ref "TP23") (pin "TP") (pinfunction "TP_TP") (pintype "input"))
      (node (ref "TP39") (pin "TP") (pinfunction "TP_TP") (pintype "input"))
      (node (ref "TP55") (pin "TP") (pinfunction "TP_TP") (pintype "input"))
      (node (ref "TP7") (pin "TP") (pinfunction "TP_TP") (pintype "input"))
      (node (ref "U14") (pin "15") (pinfunction "CC1_15") (pintype "bidirectional"))
      (node (ref "U20") (pin "15") (pinfunction "CC1_15") (pintype "bidirectional"))
      (node (ref "U3") (pin "15") (pinfunction "CC1_15") (pintype "bidirectional"))
      (node (ref "U8") (pin "15") (pinfunction "CC1_15") (pintype "bidirectional"))
    )
    (net (code "2") (name "/CC2") (class "Default")
      (node (ref "J2") (pin "B5") (pinfunction "CC2_B5") (pintype "bidirectional"))
      (node (ref "J4") (pin "B5") (pinfunction "CC2_B5") (pintype "bidirectional"))
      (node (ref "J5") (pin "B5") (pinfunction "CC2_B5") (pintype "bidirectional"))
      (node (ref "J7") (pin "B5") (pinfunction "CC2_B5") (pintype "bidirectional"))
      (node (ref "TP24") (pin "TP") (pinfunction "TP_TP") (pintype "input"))
      (node (ref "TP40") (pin "TP") (pinfunction "TP_TP") (pintype "input"))
      (node (ref "TP56") (pin "TP") (pinfunction "TP_TP") (pintype "input"))
      (node (ref "TP8") (pin "TP") (pinfunction "TP_TP") (pintype "input"))
      (node (ref "U14") (pin "14") (pinfunction "CC2_14") (pintype "bidirectional"))
      (node (ref "U20") (pin "14") (pinfunction "CC2_14") (pintype "bidirectional"))
      (node (ref "U3") (pin "14") (pinfunction "CC2_14") (pintype "bidirectional"))
      (node (ref "U8") (pin "14") (pinfunction "CC2_14") (pintype "bidirectional"))
    )
    (net (code "3") (name "/DTCT") (class "Default")
      (node (ref "JTAG") (pin "9") (pinfunction "GNDDTCT_9") (pintype "bidirectional"))
      (node (ref "JTAG2") (pin "9") (pinfunction "GNDDTCT_9") (pintype "bidirectional"))
      (node (ref "JTAG4") (pin "9") (pinfunction "GNDDTCT_9") (pintype "bidirectional"))
      (node (ref "JTAG6") (pin "9") (pinfunction "GNDDTCT_9") (pintype "bidirectional"))
    )
    (net (code "4") (name "/FAULT") (class "Default")
      (node (ref "Q15") (pin "1") (pinfunction "G_1") (pintype "bidirectional"))
      (node (ref "Q21") (pin "1") (pinfunction "G_1") (pintype "bidirectional"))
      (node (ref "Q3") (pin "1") (pinfunction "G_1") (pintype "bidirectional"))
      (node (ref "Q9") (pin "1") (pinfunction "G_1") (pintype "bidirectional"))
      (node (ref "R126") (pin "1") (pinfunction "1_1") (pintype "passive"))
      (node (ref "R186") (pin "1") (pinfunction "1_1") (pintype "passive"))
      (node (ref "R6") (pin "1") (pinfunction "1_1") (pintype "passive"))
      (node (ref "R66") (pin "1") (pinfunction "1_1") (pintype "passive"))
      (node (ref "U14") (pin "9") (pinfunction "FAULT_9") (pintype "bidirectional"))
      (node (ref "U20") (pin "9") (pinfunction "FAULT_9") (pintype "bidirectional"))
      (node (ref "U3") (pin "9") (pinfunction "FAULT_9") (pintype "bidirectional"))
      (node (ref "U8") (pin "9") (pinfunction "FAULT_9") (pintype "bidirectional"))
    )
    (net (code "5") (name "/FLIP") (class "Default")
      (node (ref "R123") (pin "2") (pinfunction "2_2") (pintype "passive"))
      (node (ref "R183") (pin "2") (pinfunction "2_2") (pintype "passive"))
      (node (ref "R3") (pin "2") (pinfunction "2_2") (pintype "passive"))
      (node (ref "R63") (pin "2") (pinfunction "2_2") (pintype "passive"))
      (node (ref "U14") (pin "10") (pinfunction "FLIP_10") (pintype "bidirectional"))
      (node (ref "U20") (pin "10") (pinfunction "FLIP_10") (pintype "bidirectional"))
      (node (ref "U3") (pin "10") (pinfunction "FLIP_10") (pintype "bidirectional"))
      (node (ref "U8") (pin "10") (pinfunction "FLIP_10") (pintype "bidirectional"))
    )
    (net (code "6") (name "/G1G2") (class "Default")
      (node (ref "C25") (pin "2") (pinfunction "2_2") (pintype "passive"))
      (node (ref "C30") (pin "2") (pinfunction "2_2") (pintype "passive"))
      (node (ref "C310") (pin "2") (pinfunction "2_2") (pintype "passive"))
      (node (ref "C311") (pin "2") (pinfunction "2_2") (pintype "passive"))
      (node (ref "C51") (pin "2") (pinfunction "2_2") (pintype "passive"))
      (node (ref "C56") (pin "2") (pinfunction "2_2") (pintype "passive"))
      (node (ref "C77") (pin "2") (pinfunction "2_2") (pintype "passive"))
      (node (ref "C82") (pin "2") (pinfunction "2_2") (pintype "passive"))
      (node (ref "D2") (pin "A") (pinfunction "A_A") (pintype "passive"))
      (node (ref "D3") (pin "A") (pinfunction "A_A") (pintype "passive"))
      (node (ref "D5") (pin "A") (pinfunction "A_A") (pintype "passive"))
      (node (ref "D7") (pin "A") (pinfunction "A_A") (pintype "passive"))
      (node (ref "Q1") (pin "2") (pinfunction "G1_2") (pintype "bidirectional"))
      (node (ref "Q1") (pin "4") (pinfunction "G2_4") (pintype "bidirectional"))
      (node (ref "Q13") (pin "2") (pinfunction "G1_2") (pintype "bidirectional"))
      (node (ref "Q13") (pin "4") (pinfunction "G2_4") (pintype "bidirectional"))
      (node (ref "Q19") (pin "2") (pinfunction "G1_2") (pintype "bidirectional"))
      (node (ref "Q19") (pin "4") (pinfunction "G2_4") (pintype "bidirectional"))
      (node (ref "Q7") (pin "2") (pinfunction "G1_2") (pintype "bidirectional"))
      (node (ref "Q7") (pin "4") (pinfunction "G2_4") (pintype "bidirectional"))
      (node (ref "R117") (pin "1") (pinfunction "1_1") (pintype "passive"))
      (node (ref "R118") (pin "2") (pinfunction "2_2") (pintype "passive"))
      (node (ref "R119") (pin "2") (pinfunction "2_2") (pintype "passive"))
      (node (ref "R177") (pin "1") (pinfunction "1_1") (pintype "passive"))
      (node (ref "R178") (pin "2") (pinfunction "2_2") (pintype "passive"))
      (node (ref "R179") (pin "2") (pinfunction "2_2") (pintype "passive"))
      (node (ref "R310") (pin "2") (pinfunction "2_2") (pintype "passive"))
      (node (ref "R311") (pin "1") (pinfunction "1_1") (pintype "passive"))
      (node (ref "R312") (pin "2") (pinfunction "2_2") (pintype "passive"))
      (node (ref "R57") (pin "1") (pinfunction "1_1") (pintype "passive"))
      (node (ref "R58") (pin "2") (pinfunction "2_2") (pintype "passive"))
      (node (ref "R59") (pin "2") (pinfunction "2_2") (pintype "passive"))
      (node (ref "TP19") (pin "TP") (pinfunction "TP_TP") (pintype "input"))
      (node (ref "TP3") (pin "TP") (pinfunction "TP_TP") (pintype "input"))
      (node (ref "TP35") (pin "TP") (pinfunction "TP_TP") (pintype "input"))
      (node (ref "TP51") (pin "TP") (pinfunction "TP_TP") (pintype "input"))
    )
    (net (code "7") (name "/G3G4") (class "Default")
      (node (ref "Q14") (pin "2") (pinfunction "G1_2") (pintype "bidirectional"))
      (node (ref "Q14") (pin "4") (pinfunction "G2_4") (pintype "bidirectional"))
      (node (ref "Q2") (pin "2") (pinfunction "G1_2") (pintype "bidirectional"))
      (node (ref "Q2") (pin "4") (pinfunction "G2_4") (pintype "bidirectional"))
      (node (ref "Q20") (pin "2") (pinfunction "G1_2") (pintype "bidirectional"))
      (node (ref "Q20") (pin "4") (pinfunction "G2_4") (pintype "bidirectional"))
      (node (ref "Q8") (pin "2") (pinfunction "G1_2") (pintype "bidirectional"))
      (node (ref "Q8") (pin "4") (pinfunction "G2_4") (pintype "bidirectional"))
      (node (ref "R120") (pin "1") (pinfunction "1_1") (pintype "passive"))
      (node (ref "R121") (pin "2") (pinfunction "2_2") (pintype "passive"))
      (node (ref "R180") (pin "1") (pinfunction "1_1") (pintype "passive"))
      (node (ref "R181") (pin "2") (pinfunction "2_2") (pintype "passive"))
      (node (ref "R320") (pin "1") (pinfunction "1_1") (pintype "passive"))
      (node (ref "R321") (pin "2") (pinfunction "2_2") (pintype "passive"))
      (node (ref "R60") (pin "1") (pinfunction "1_1") (pintype "passive"))
      (node (ref "R61") (pin "2") (pinfunction "2_2") (pintype "passive"))
      (node (ref "TP20") (pin "TP") (pinfunction "TP_TP") (pintype "input"))
      (node (ref "TP36") (pin "TP") (pinfunction "TP_TP") (pintype "input"))
      (node (ref "TP4") (pin "TP") (pinfunction "TP_TP") (pintype "input"))
      (node (ref "TP52") (pin "TP") (pinfunction "TP_TP") (pintype "input"))
    )
    (net (code "8") (name "/KEY") (class "Default")
      (node (ref "JTAG") (pin "7") (pinfunction "KEY_7") (pintype "bidirectional"))
      (node (ref "JTAG2") (pin "7") (pinfunction "KEY_7") (pintype "bidirectional"))
      (node (ref "JTAG4") (pin "7") (pinfunction "KEY_7") (pintype "bidirectional"))
      (node (ref "JTAG6") (pin "7") (pinfunction "KEY_7") (pintype "bidirectional"))
    )
    (net (code "9") (name "/LED") (class "Default")
      (node (ref "R11") (pin "2") (pinfunction "2_2") (pintype "passive"))
      (node (ref "R129") (pin "2") (pinfunction "2_2") (pintype "passive"))
      (node (ref "R189") (pin "2") (pinfunction "2_2") (pintype "passive"))
      (node (ref "R69") (pin "2") (pinfunction "2_2") (pintype "passive"))
      (node (ref "U1") (pin "8") (pinfunction "PA07_8") (pintype "bidirectional"))
      (node (ref "U15") (pin "8") (pinfunction "PA07_8") (pintype "bidirectional"))
      (node (ref "U21") (pin "8") (pinfunction "PA07_8") (pintype "bidirectional"))
      (node (ref "U9") (pin "8") (pinfunction "PA07_8") (pintype "bidirectional"))
    )
    (net (code "10") (name "/P14") (class "Default")
      (node (ref "SV10") (pin "10") (pinfunction "10_10") (pintype "passive"))
      (node (ref "SV14") (pin "10") (pinfunction "10_10") (pintype "passive"))
      (node (ref "SV2") (pin "10") (pinfunction "10_10") (pintype "passive"))
      (node (ref "SV6") (pin "10") (pinfunction "10_10") (pintype "passive"))
      (node (ref "U1") (pin "14") (pinfunction "PA11_14") (pintype "bidirectional"))
      (node (ref "U15") (pin "14") (pinfunction "PA11_14") (pintype "bidirectional"))
      (node (ref "U21") (pin "14") (pinfunction "PA11_14") (pintype "bidirectional"))
      (node (ref "U9") (pin "14") (pinfunction "PA11_14") (pintype "bidirectional"))
    )
    (net (code "11") (name "/P15") (class "Default")
      (node (ref "SV10") (pin "9") (pinfunction "9_9") (pintype "passive"))
      (node (ref "SV14") (pin "9") (pinfunction "9_9") (pintype "passive"))
      (node (ref "SV2") (pin "9") (pinfunction "9_9") (pintype "passive"))
      (node (ref "SV6") (pin "9") (pinfunction "9_9") (pintype "passive"))
      (node (ref "U1") (pin "15") (pinfunction "PA14_15") (pintype "bidirectional"))
      (node (ref "U15") (pin "15") (pinfunction "PA14_15") (pintype "bidirectional"))
      (node (ref "U21") (pin "15") (pinfunction "PA14_15") (pintype "bidirectional"))
      (node (ref "U9") (pin "15") (pinfunction "PA14_15") (pintype "bidirectional"))
    )
    (net (code "12") (name "/P16") (class "Default")
      (node (ref "SV10") (pin "8") (pinfunction "8_8") (pintype "passive"))
      (node (ref "SV14") (pin "8") (pinfunction "8_8") (pintype "passive"))
      (node (ref "SV2") (pin "8") (pinfunction "8_8") (pintype "passive"))
      (node (ref "SV6") (pin "8") (pinfunction "8_8") (pintype "passive"))
      (node (ref "U1") (pin "16") (pinfunction "PA15_16") (pintype "bidirectional"))
      (node (ref "U15") (pin "16") (pinfunction "PA15_16") (pintype "bidirectional"))
      (node (ref "U21") (pin "16") (pinfunction "PA15_16") (pintype "bidirectional"))
      (node (ref "U9") (pin "16") (pinfunction "PA15_16") (pintype "bidirectional"))
    )
    (net (code "13") (name "/P17") (class "Default")
      (node (ref "SV10") (pin "7") (pinfunction "7_7") (pintype "passive"))
      (node (ref "SV14") (pin "7") (pinfunction "7_7") (pintype "passive"))
      (node (ref "SV2") (pin "7") (pinfunction "7_7") (pintype "passive"))
      (node (ref "SV6") (pin "7") (pinfunction "7_7") (pintype "passive"))
      (node (ref "U1") (pin "17") (pinfunction "PA16_17") (pintype "bidirectional"))
      (node (ref "U15") (pin "17") (pinfunction "PA16_17") (pintype "bidirectional"))
      (node (ref "U21") (pin "17") (pinfunction "PA16_17") (pintype "bidirectional"))
      (node (ref "U9") (pin "17") (pinfunction "PA16_17") (pintype "bidirectional"))
    )
    (net (code "14") (name "/P18") (class "Default")
      (node (ref "SV10") (pin "6") (pinfunction "6_6") (pintype "passive"))
      (node (ref "SV14") (pin "6") (pinfunction "6_6") (pintype "passive"))
      (node (ref "SV2") (pin "6") (pinfunction "6_6") (pintype "passive"))
      (node (ref "SV6") (pin "6") (pinfunction "6_6") (pintype "passive"))
      (node (ref "U1") (pin "18") (pinfunction "PA17_18") (pintype "bidirectional"))
      (node (ref "U15") (pin "18") (pinfunction "PA17_18") (pintype "bidirectional"))
      (node (ref "U21") (pin "18") (pinfunction "PA17_18") (pintype "bidirectional"))
      (node (ref "U9") (pin "18") (pinfunction "PA17_18") (pintype "bidirectional"))
    )
    (net (code "15") (name "/P19") (class "Default")
      (node (ref "SV10") (pin "5") (pinfunction "5_5") (pintype "passive"))
      (node (ref "SV14") (pin "5") (pinfunction "5_5") (pintype "passive"))
      (node (ref "SV2") (pin "5") (pinfunction "5_5") (pintype "passive"))
      (node (ref "SV6") (pin "5") (pinfunction "5_5") (pintype "passive"))
      (node (ref "U1") (pin "19") (pinfunction "PA18_19") (pintype "bidirectional"))
      (node (ref "U15") (pin "19") (pinfunction "PA18_19") (pintype "bidirectional"))
      (node (ref "U21") (pin "19") (pinfunction "PA18_19") (pintype "bidirectional"))
      (node (ref "U9") (pin "19") (pinfunction "PA18_19") (pintype "bidirectional"))
    )
    (net (code "16") (name "/P20") (class "Default")
      (node (ref "SV10") (pin "4") (pinfunction "4_4") (pintype "passive"))
      (node (ref "SV14") (pin "4") (pinfunction "4_4") (pintype "passive"))
      (node (ref "SV2") (pin "4") (pinfunction "4_4") (pintype "passive"))
      (node (ref "SV6") (pin "4") (pinfunction "4_4") (pintype "passive"))
      (node (ref "U1") (pin "20") (pinfunction "PA19_20") (pintype "bidirectional"))
      (node (ref "U15") (pin "20") (pinfunction "PA19_20") (pintype "bidirectional"))
      (node (ref "U21") (pin "20") (pinfunction "PA19_20") (pintype "bidirectional"))
      (node (ref "U9") (pin "20") (pinfunction "PA19_20") (pintype "bidirectional"))
    )
    (net (code "17") (name "/P21") (class "Default")
      (node (ref "SV10") (pin "3") (pinfunction "3_3") (pintype "passive"))
      (node (ref "SV14") (pin "3") (pinfunction "3_3") (pintype "passive"))
      (node (ref "SV2") (pin "3") (pinfunction "3_3") (pintype "passive"))
      (node (ref "SV6") (pin "3") (pinfunction "3_3") (pintype "passive"))
      (node (ref "U1") (pin "21") (pinfunction "PA22_21") (pintype "bidirectional"))
      (node (ref "U15") (pin "21") (pinfunction "PA22_21") (pintype "bidirectional"))
      (node (ref "U21") (pin "21") (pinfunction "PA22_21") (pintype "bidirectional"))
      (node (ref "U9") (pin "21") (pinfunction "PA22_21") (pintype "bidirectional"))
    )
    (net (code "18") (name "/P22") (class "Default")
      (node (ref "SV10") (pin "2") (pinfunction "2_2") (pintype "passive"))
      (node (ref "SV14") (pin "2") (pinfunction "2_2") (pintype "passive"))
      (node (ref "SV2") (pin "2") (pinfunction "2_2") (pintype "passive"))
      (node (ref "SV6") (pin "2") (pinfunction "2_2") (pintype "passive"))
      (node (ref "U1") (pin "22") (pinfunction "PA23_22") (pintype "bidirectional"))
      (node (ref "U15") (pin "22") (pinfunction "PA23_22") (pintype "bidirectional"))
      (node (ref "U21") (pin "22") (pinfunction "PA23_22") (pintype "bidirectional"))
      (node (ref "U9") (pin "22") (pinfunction "PA23_22") (pintype "bidirectional"))
    )
    (net (code "19") (name "/S1S2") (class "Default")
      (node (ref "D2") (pin "C") (pinfunction "K_C") (pintype "passive"))
      (node (ref "D3") (pin "C") (pinfunction "K_C") (pintype "passive"))
      (node (ref "D5") (pin "C") (pinfunction "K_C") (pintype "passive"))
      (node (ref "D7") (pin "C") (pinfunction "K_C") (pintype "passive"))
      (node (ref "Q1") (pin "1") (pinfunction "S1_1") (pintype "bidirectional"))
      (node (ref "Q1") (pin "3") (pinfunction "S2_3") (pintype "bidirectional"))
      (node (ref "Q13") (pin "1") (pinfunction "S1_1") (pintype "bidirectional"))
      (node (ref "Q13") (pin "3") (pinfunction "S2_3") (pintype "bidirectional"))
      (node (ref "Q19") (pin "1") (pinfunction "S1_1") (pintype "bidirectional"))
      (node (ref "Q19") (pin "3") (pinfunction "S2_3") (pintype "bidirectional"))
      (node (ref "Q7") (pin "1") (pinfunction "S1_1") (pintype "bidirectional"))
      (node (ref "Q7") (pin "3") (pinfunction "S2_3") (pintype "bidirectional"))
      (node (ref "R119") (pin "1") (pinfunction "1_1") (pintype "passive"))
      (node (ref "R179") (pin "1") (pinfunction "1_1") (pintype "passive"))
      (node (ref "R310") (pin "1") (pinfunction "1_1") (pintype "passive"))
      (node (ref "R59") (pin "1") (pinfunction "1_1") (pintype "passive"))
    )
    (net (code "20") (name "/S3S4") (class "Default")
      (node (ref "Q14") (pin "1") (pinfunction "S1_1") (pintype "bidirectional"))
      (node (ref "Q14") (pin "3") (pinfunction "S2_3") (pintype "bidirectional"))
      (node (ref "Q2") (pin "1") (pinfunction "S1_1") (pintype "bidirectional"))
      (node (ref "Q2") (pin "3") (pinfunction "S2_3") (pintype "bidirectional"))
      (node (ref "Q20") (pin "1") (pinfunction "S1_1") (pintype "bidirectional"))
      (node (ref "Q20") (pin "3") (pinfunction "S2_3") (pintype "bidirectional"))
      (node (ref "Q8") (pin "1") (pinfunction "S1_1") (pintype "bidirectional"))
      (node (ref "Q8") (pin "3") (pinfunction "S2_3") (pintype "bidirectional"))
    )
    (net (code "21") (name "/SAFE_PWR_EN") (class "Default")
      (node (ref "R120") (pin "2") (pinfunction "2_2") (pintype "passive"))
      (node (ref "R180") (pin "2") (pinfunction "2_2") (pintype "passive"))
      (node (ref "R320") (pin "2") (pinfunction "2_2") (pintype "passive"))
      (node (ref "R60") (pin "2") (pinfunction "2_2") (pintype "passive"))
      (node (ref "U14") (pin "4") (pinfunction "SAFE_PWR_EN_4") (pintype "bidirectional"))
      (node (ref "U20") (pin "4") (pinfunction "SAFE_PWR_EN_4") (pintype "bidirectional"))
      (node (ref "U3") (pin "4") (pinfunction "SAFE_PWR_EN_4") (pintype "bidirectional"))
      (node (ref "U8") (pin "4") (pinfunction "SAFE_PWR_EN_4") (pintype "bidirectional"))
    )
    (net (code "22") (name "/SWO") (class "Default")
      (node (ref "JTAG") (pin "6") (pinfunction "SWO/TDO_6") (pintype "bidirectional"))
      (node (ref "JTAG2") (pin "6") (pinfunction "SWO/TDO_6") (pintype "bidirectional"))
      (node (ref "JTAG4") (pin "6") (pinfunction "SWO/TDO_6") (pintype "bidirectional"))
      (node (ref "JTAG6") (pin "6") (pinfunction "SWO/TDO_6") (pintype "bidirectional"))
    )
    (net (code "23") (name "/VBUS") (class "Default")
      (node (ref "C1") (pin "1") (pinfunction "1_1") (pintype "passive"))
      (node (ref "C30") (pin "1") (pinfunction "1_1") (pintype "passive"))
      (node (ref "C31") (pin "1") (pinfunction "1_1") (pintype "passive"))
      (node (ref "C310") (pin "1") (pinfunction "1_1") (pintype "passive"))
      (node (ref "C56") (pin "1") (pinfunction "1_1") (pintype "passive"))
      (node (ref "C57") (pin "1") (pinfunction "1_1") (pintype "passive"))
      (node (ref "C82") (pin "1") (pinfunction "1_1") (pintype "passive"))
      (node (ref "C83") (pin "1") (pinfunction "1_1") (pintype "passive"))
      (node (ref "FAULT") (pin "A") (pinfunction "A_A") (pintype "passive"))
      (node (ref "FAULT2") (pin "A") (pinfunction "A_A") (pintype "passive"))
      (node (ref "FAULT4") (pin "A") (pinfunction "A_A") (pintype "passive"))
      (node (ref "FAULT6") (pin "A") (pinfunction "A_A") (pintype "passive"))
      (node (ref "J2") (pin "A4_B9") (pinfunction "VBUS_A4_B9") (pintype "power_in"))
      (node (ref "J2") (pin "B4_A9") (pinfunction "VBUS_B4_A9") (pintype "power_in"))
      (node (ref "J4") (pin "A4_B9") (pinfunction "VBUS_A4_B9") (pintype "power_in"))
      (node (ref "J4") (pin "B4_A9") (pinfunction "VBUS_B4_A9") (pintype "power_in"))
      (node (ref "J5") (pin "A4_B9") (pinfunction "VBUS_A4_B9") (pintype "power_in"))
      (node (ref "J5") (pin "B4_A9") (pinfunction "VBUS_B4_A9") (pintype "power_in"))
      (node (ref "J7") (pin "A4_B9") (pinfunction "VBUS_A4_B9") (pintype "power_in"))
      (node (ref "J7") (pin "B4_A9") (pinfunction "VBUS_B4_A9") (pintype "power_in"))
      (node (ref "Q1") (pin "5") (pinfunction "D2_1_5") (pintype "bidirectional"))
      (node (ref "Q1") (pin "6") (pinfunction "D2_2_6") (pintype "bidirectional"))
      (node (ref "Q13") (pin "5") (pinfunction "D2_1_5") (pintype "bidirectional"))
      (node (ref "Q13") (pin "6") (pinfunction "D2_2_6") (pintype "bidirectional"))
      (node (ref "Q14") (pin "7") (pinfunction "D1_1_7") (pintype "bidirectional"))
      (node (ref "Q14") (pin "8") (pinfunction "D1_2_8") (pintype "bidirectional"))
      (node (ref "Q19") (pin "5") (pinfunction "D2_1_5") (pintype "bidirectional"))
      (node (ref "Q19") (pin "6") (pinfunction "D2_2_6") (pintype "bidirectional"))
      (node (ref "Q2") (pin "7") (pinfunction "D1_1_7") (pintype "bidirectional"))
      (node (ref "Q2") (pin "8") (pinfunction "D1_2_8") (pintype "bidirectional"))
      (node (ref "Q20") (pin "7") (pinfunction "D1_1_7") (pintype "bidirectional"))
      (node (ref "Q20") (pin "8") (pinfunction "D1_2_8") (pintype "bidirectional"))
      (node (ref "Q7") (pin "5") (pinfunction "D2_1_5") (pintype "bidirectional"))
      (node (ref "Q7") (pin "6") (pinfunction "D2_2_6") (pintype "bidirectional"))
      (node (ref "Q8") (pin "7") (pinfunction "D1_1_7") (pintype "bidirectional"))
      (node (ref "Q8") (pin "8") (pinfunction "D1_2_8") (pintype "bidirectional"))
      (node (ref "R118") (pin "1") (pinfunction "1_1") (pintype "passive"))
      (node (ref "R121") (pin "1") (pinfunction "1_1") (pintype "passive"))
      (node (ref "R178") (pin "1") (pinfunction "1_1") (pintype "passive"))
      (node (ref "R181") (pin "1") (pinfunction "1_1") (pintype "passive"))
      (node (ref "R312") (pin "1") (pinfunction "1_1") (pintype "passive"))
      (node (ref "R321") (pin "1") (pinfunction "1_1") (pintype "passive"))
      (node (ref "R58") (pin "1") (pinfunction "1_1") (pintype "passive"))
      (node (ref "R61") (pin "1") (pinfunction "1_1") (pintype "passive"))
      (node (ref "SV1") (pin "4") (pinfunction "4_4") (pintype "passive"))
      (node (ref "SV13") (pin "4") (pinfunction "4_4") (pintype "passive"))
      (node (ref "SV5") (pin "4") (pinfunction "4_4") (pintype "passive"))
      (node (ref "SV9") (pin "4") (pinfunction "4_4") (pintype "passive"))
      (node (ref "TP1") (pin "TP") (pinfunction "TP_TP") (pintype "input"))
      (node (ref "TP17") (pin "TP") (pinfunction "TP_TP") (pintype "input"))
      (node (ref "TP33") (pin "TP") (pinfunction "TP_TP") (pintype "input"))
      (node (ref "TP49") (pin "TP") (pinfunction "TP_TP") (pintype "input"))
      (node (ref "U14") (pin "18") (pinfunction "VBUS_IN_18") (pintype "bidirectional"))
      (node (ref "U20") (pin "18") (pinfunction "VBUS_IN_18") (pintype "bidirectional"))
      (node (ref "U3") (pin "18") (pinfunction "VBUS_IN_18") (pintype "bidirectional"))
      (node (ref "U8") (pin "18") (pinfunction "VBUS_IN_18") (pintype "bidirectional"))
    )
    (net (code "24") (name "/VBUS_FET_EN") (class "Default")
      (node (ref "R117") (pin "2") (pinfunction "2_2") (pintype "passive"))
      (node (ref "R177") (pin "2") (pinfunction "2_2") (pintype "passive"))
      (node (ref "R311") (pin "2") (pinfunction "2_2") (pintype "passive"))
      (node (ref "R57") (pin "2") (pinfunction "2_2") (pintype "passive"))
      (node (ref "U14") (pin "3") (pinfunction "VBUS_FET_EN_3") (pintype "bidirectional"))
      (node (ref "U20") (pin "3") (pinfunction "VBUS_FET_EN_3") (pintype "bidirectional"))
      (node (ref "U3") (pin "3") (pinfunction "VBUS_FET_EN_3") (pintype "bidirectional"))
      (node (ref "U8") (pin "3") (pinfunction "VBUS_FET_EN_3") (pintype "bidirectional"))
    )
    (net (code "25") (name "/VCCD") (class "Default")
      (node (ref "C29") (pin "1") (pinfunction "1_1") (pintype "passive"))
      (node (ref "C304") (pin "1") (pinfunction "1_1") (pintype "passive"))
      (node (ref "C55") (pin "1") (pinfunction "1_1") (pintype "passive"))
      (node (ref "C81") (pin "1") (pinfunction "1_1") (pintype "passive"))
      (node (ref "TP22") (pin "TP") (pinfunction "TP_TP") (pintype "input"))
      (node (ref "TP38") (pin "TP") (pinfunction "TP_TP") (pintype "input"))
      (node (ref "TP54") (pin "TP") (pinfunction "TP_TP") (pintype "input"))
      (node (ref "TP6") (pin "TP") (pinfunction "TP_TP") (pintype "input"))
      (node (ref "U14") (pin "24") (pinfunction "VCCD_24") (pintype "bidirectional"))
      (node (ref "U20") (pin "24") (pinfunction "VCCD_24") (pintype "bidirectional"))
      (node (ref "U3") (pin "24") (pinfunction "VCCD_24") (pintype "bidirectional"))
      (node (ref "U8") (pin "24") (pinfunction "VCCD_24") (pintype "bidirectional"))
    )
    (net (code "26") (name "/VDDCORE") (class "Default")
      (node (ref "C32") (pin "1") (pinfunction "1_1") (pintype "passive"))
      (node (ref "C58") (pin "1") (pinfunction "1_1") (pintype "passive"))
      (node (ref "C6") (pin "1") (pinfunction "1_1") (pintype "passive"))
      (node (ref "C84") (pin "1") (pinfunction "1_1") (pintype "passive"))
      (node (ref "U1") (pin "29") (pinfunction "VDDCORE_29") (pintype "power_in"))
      (node (ref "U15") (pin "29") (pinfunction "VDDCORE_29") (pintype "power_in"))
      (node (ref "U21") (pin "29") (pinfunction "VDDCORE_29") (pintype "power_in"))
      (node (ref "U9") (pin "29") (pinfunction "VDDCORE_29") (pintype "power_in"))
    )
    (net (code "27") (name "/VDDD") (class "Default")
      (node (ref "C26") (pin "1") (pinfunction "1_1") (pintype "passive"))
      (node (ref "C27") (pin "1") (pinfunction "1_1") (pintype "passive"))
      (node (ref "C28") (pin "1") (pinfunction "1_1") (pintype "passive"))
      (node (ref "C301") (pin "1") (pinfunction "1_1") (pintype "passive"))
      (node (ref "C302") (pin "1") (pinfunction "1_1") (pintype "passive"))
      (node (ref "C303") (pin "1") (pinfunction "1_1") (pintype "passive"))
      (node (ref "C52") (pin "1") (pinfunction "1_1") (pintype "passive"))
      (node (ref "C53") (pin "1") (pinfunction "1_1") (pintype "passive"))
      (node (ref "C54") (pin "1") (pinfunction "1_1") (pintype "passive"))
      (node (ref "C78") (pin "1") (pinfunction "1_1") (pintype "passive"))
      (node (ref "C79") (pin "1") (pinfunction "1_1") (pintype "passive"))
      (node (ref "C80") (pin "1") (pinfunction "1_1") (pintype "passive"))
      (node (ref "TP21") (pin "TP") (pinfunction "TP_TP") (pintype "input"))
      (node (ref "TP37") (pin "TP") (pinfunction "TP_TP") (pintype "input"))
      (node (ref "TP5") (pin "TP") (pinfunction "TP_TP") (pintype "input"))
      (node (ref "TP53") (pin "TP") (pinfunction "TP_TP") (pintype "input"))
      (node (ref "U14") (pin "23") (pinfunction "VDDD_23") (pintype "bidirectional"))
      (node (ref "U20") (pin "23") (pinfunction "VDDD_23") (pintype "bidirectional"))
      (node (ref "U3") (pin "23") (pinfunction "VDDD_23") (pintype "bidirectional"))
      (node (ref "U8") (pin "23") (pinfunction "VDDD_23") (pintype "bidirectional"))
    )
    (net (code "28") (name "/VDDOUT") (class "Default")
      (node (ref "C2") (pin "1") (pinfunction "1_1") (pintype "passive"))
      (node (ref "C21") (pin "1") (pinfunction "1_1") (pintype "passive"))
      (node (ref "C25") (pin "1") (pinfunction "1_1") (pintype "passive"))
      (node (ref "C311") (pin "1") (pinfunction "1_1") (pintype "passive"))
      (node (ref "C47") (pin "1") (pinfunction "1_1") (pintype "passive"))
      (node (ref "C51") (pin "1") (pinfunction "1_1") (pintype "passive"))
      (node (ref "C73") (pin "1") (pinfunction "1_1") (pintype "passive"))
      (node (ref "C77") (pin "1") (pinfunction "1_1") (pintype "passive"))
      (node (ref "Q1") (pin "7") (pinfunction "D1_1_7") (pintype "bidirectional"))
      (node (ref "Q1") (pin "8") (pinfunction "D1_2_8") (pintype "bidirectional"))
      (node (ref "Q13") (pin "7") (pinfunction "D1_1_7") (pintype "bidirectional"))
      (node (ref "Q13") (pin "8") (pinfunction "D1_2_8") (pintype "bidirectional"))
      (node (ref "Q14") (pin "5") (pinfunction "D2_1_5") (pintype "bidirectional"))
      (node (ref "Q14") (pin "6") (pinfunction "D2_2_6") (pintype "bidirectional"))
      (node (ref "Q19") (pin "7") (pinfunction "D1_1_7") (pintype "bidirectional"))
      (node (ref "Q19") (pin "8") (pinfunction "D1_2_8") (pintype "bidirectional"))
      (node (ref "Q2") (pin "5") (pinfunction "D2_1_5") (pintype "bidirectional"))
      (node (ref "Q2") (pin "6") (pinfunction "D2_2_6") (pintype "bidirectional"))
      (node (ref "Q20") (pin "5") (pinfunction "D2_1_5") (pintype "bidirectional"))
      (node (ref "Q20") (pin "6") (pinfunction "D2_2_6") (pintype "bidirectional"))
      (node (ref "Q7") (pin "7") (pinfunction "D1_1_7") (pintype "bidirectional"))
      (node (ref "Q7") (pin "8") (pinfunction "D1_2_8") (pintype "bidirectional"))
      (node (ref "Q8") (pin "5") (pinfunction "D2_1_5") (pintype "bidirectional"))
      (node (ref "Q8") (pin "6") (pinfunction "D2_2_6") (pintype "bidirectional"))
      (node (ref "SV1") (pin "3") (pinfunction "3_3") (pintype "passive"))
      (node (ref "SV13") (pin "3") (pinfunction "3_3") (pintype "passive"))
      (node (ref "SV5") (pin "3") (pinfunction "3_3") (pintype "passive"))
      (node (ref "SV9") (pin "3") (pinfunction "3_3") (pintype "passive"))
      (node (ref "TP18") (pin "TP") (pinfunction "TP_TP") (pintype "input"))
      (node (ref "TP2") (pin "TP") (pinfunction "TP_TP") (pintype "input"))
      (node (ref "TP34") (pin "TP") (pinfunction "TP_TP") (pintype "input"))
      (node (ref "TP50") (pin "TP") (pinfunction "TP_TP") (pintype "input"))
      (node (ref "U13") (pin "3") (pinfunction "IN_3") (pintype "input"))
      (node (ref "U14") (pin "11") (pinfunction "VDC_OUT_11") (pintype "bidirectional"))
      (node (ref "U19") (pin "3") (pinfunction "IN_3") (pintype "input"))
      (node (ref "U2") (pin "3") (pinfunction "IN_3") (pintype "input"))
      (node (ref "U20") (pin "11") (pinfunction "VDC_OUT_11") (pintype "bidirectional"))
      (node (ref "U3") (pin "11") (pinfunction "VDC_OUT_11") (pintype "bidirectional"))
      (node (ref "U7") (pin "3") (pinfunction "IN_3") (pintype "input"))
      (node (ref "U8") (pin "11") (pinfunction "VDC_OUT_11") (pintype "bidirectional"))
    )
    (net (code "29") (name "/_SCL") (class "Default")
      (node (ref "R12") (pin "1") (pinfunction "1_1") (pintype "passive"))
      (node (ref "R132") (pin "1") (pinfunction "1_1") (pintype "passive"))
      (node (ref "R192") (pin "1") (pinfunction "1_1") (pintype "passive"))
      (node (ref "R72") (pin "1") (pinfunction "1_1") (pintype "passive"))
      (node (ref "U1") (pin "12") (pinfunction "PA09_12") (pintype "bidirectional"))
      (node (ref "U15") (pin "12") (pinfunction "PA09_12") (pintype "bidirectional"))
      (node (ref "U21") (pin "12") (pinfunction "PA09_12") (pintype "bidirectional"))
      (node (ref "U9") (pin "12") (pinfunction "PA09_12") (pintype "bidirectional"))
    )
    (net (code "30") (name "/_SDA") (class "Default")
      (node (ref "R13") (pin "1") (pinfunction "1_1") (pintype "passive"))
      (node (ref "R133") (pin "1") (pinfunction "1_1") (pintype "passive"))
      (node (ref "R193") (pin "1") (pinfunction "1_1") (pintype "passive"))
      (node (ref "R73") (pin "1") (pinfunction "1_1") (pintype "passive"))
      (node (ref "U1") (pin "11") (pinfunction "PA08_11") (pintype "bidirectional"))
      (node (ref "U15") (pin "11") (pinfunction "PA08_11") (pintype "bidirectional"))
      (node (ref "U21") (pin "11") (pinfunction "PA08_11") (pintype "bidirectional"))
      (node (ref "U9") (pin "11") (pinfunction "PA08_11") (pintype "bidirectional"))
    )
    (net (code "31") (name "/_USB_D_N") (class "Default")
      (node (ref "R130") (pin "2") (pinfunction "2_2") (pintype "passive"))
      (node (ref "R190") (pin "2") (pinfunction "2_2") (pintype "passive"))
      (node (ref "R70") (pin "2") (pinfunction "2_2") (pintype "passive"))
      (node (ref "R9") (pin "2") (pinfunction "2_2") (pintype "passive"))
      (node (ref "U1") (pin "23") (pinfunction "PA24_23") (pintype "bidirectional"))
      (node (ref "U15") (pin "23") (pinfunction "PA24_23") (pintype "bidirectional"))
      (node (ref "U21") (pin "23") (pinfunction "PA24_23") (pintype "bidirectional"))
      (node (ref "U9") (pin "23") (pinfunction "PA24_23") (pintype "bidirectional"))
    )
    (net (code "32") (name "/_USB_D_P") (class "Default")
      (node (ref "R10") (pin "2") (pinfunction "2_2") (pintype "passive"))
      (node (ref "R131") (pin "2") (pinfunction "2_2") (pintype "passive"))
      (node (ref "R191") (pin "2") (pinfunction "2_2") (pintype "passive"))
      (node (ref "R71") (pin "2") (pinfunction "2_2") (pintype "passive"))
      (node (ref "U1") (pin "24") (pinfunction "PA25_24") (pintype "bidirectional"))
      (node (ref "U15") (pin "24") (pinfunction "PA25_24") (pintype "bidirectional"))
      (node (ref "U21") (pin "24") (pinfunction "PA25_24") (pintype "bidirectional"))
      (node (ref "U9") (pin "24") (pinfunction "PA25_24") (pintype "bidirectional"))
    )
    (net (code "33") (name "3V3") (class "Default")
      (node (ref "C22") (pin "1") (pinfunction "1_1") (pintype "passive"))
      (node (ref "C23") (pin "1") (pinfunction "1_1") (pintype "passive"))
      (node (ref "C24") (pin "1") (pinfunction "1_1") (pintype "passive"))
      (node (ref "C3") (pin "1") (pinfunction "1_1") (pintype "passive"))
      (node (ref "C4") (pin "1") (pinfunction "1_1") (pintype "passive"))
      (node (ref "C48") (pin "1") (pinfunction "1_1") (pintype "passive"))
      (node (ref "C49") (pin "1") (pinfunction "1_1") (pintype "passive"))
      (node (ref "C5") (pin "1") (pinfunction "1_1") (pintype "passive"))
      (node (ref "C50") (pin "1") (pinfunction "1_1") (pintype "passive"))
      (node (ref "C74") (pin "1") (pinfunction "1_1") (pintype "passive"))
      (node (ref "C75") (pin "1") (pinfunction "1_1") (pintype "passive"))
      (node (ref "C76") (pin "1") (pinfunction "1_1") (pintype "passive"))
      (node (ref "R108") (pin "2") (pinfunction "2_2") (pintype "passive"))
      (node (ref "R110") (pin "2") (pinfunction "2_2") (pintype "passive"))
      (node (ref "R112") (pin "2") (pinfunction "2_2") (pintype "passive"))
      (node (ref "R114") (pin "2") (pinfunction "2_2") (pintype "passive"))
      (node (ref "R116") (pin "2") (pinfunction "2_2") (pintype "passive"))
      (node (ref "R123") (pin "1") (pinfunction "1_1") (pintype "passive"))
      (node (ref "R124") (pin "1") (pinfunction "1_1") (pintype "passive"))
      (node (ref "R125") (pin "1") (pinfunction "1_1") (pintype "passive"))
      (node (ref "R127") (pin "2") (pinfunction "2_2") (pintype "passive"))
      (node (ref "R134") (pin "2") (pinfunction "2_2") (pintype "passive"))
      (node (ref "R14") (pin "2") (pinfunction "2_2") (pintype "passive"))
      (node (ref "R168") (pin "2") (pinfunction "2_2") (pintype "passive"))
      (node (ref "R170") (pin "2") (pinfunction "2_2") (pintype "passive"))
      (node (ref "R172") (pin "2") (pinfunction "2_2") (pintype "passive"))
      (node (ref "R174") (pin "2") (pinfunction "2_2") (pintype "passive"))
      (node (ref "R176") (pin "2") (pinfunction "2_2") (pintype "passive"))
      (node (ref "R183") (pin "1") (pinfunction "1_1") (pintype "passive"))
      (node (ref "R184") (pin "1") (pinfunction "1_1") (pintype "passive"))
      (node (ref "R185") (pin "1") (pinfunction "1_1") (pintype "passive"))
      (node (ref "R187") (pin "2") (pinfunction "2_2") (pintype "passive"))
      (node (ref "R194") (pin "2") (pinfunction "2_2") (pintype "passive"))
      (node (ref "R2") (pin "2") (pinfunction "2_2") (pintype "passive"))
      (node (ref "R3") (pin "1") (pinfunction "1_1") (pintype "passive"))
      (node (ref "R301") (pin "2") (pinfunction "2_2") (pintype "passive"))
      (node (ref "R303") (pin "2") (pinfunction "2_2") (pintype "passive"))
      (node (ref "R305") (pin "2") (pinfunction "2_2") (pintype "passive"))
      (node (ref "R307") (pin "2") (pinfunction "2_2") (pintype "passive"))
      (node (ref "R4") (pin "1") (pinfunction "1_1") (pintype "passive"))
      (node (ref "R48") (pin "2") (pinfunction "2_2") (pintype "passive"))
      (node (ref "R5") (pin "1") (pinfunction "1_1") (pintype "passive"))
      (node (ref "R50") (pin "2") (pinfunction "2_2") (pintype "passive"))
      (node (ref "R52") (pin "2") (pinfunction "2_2") (pintype "passive"))
      (node (ref "R54") (pin "2") (pinfunction "2_2") (pintype "passive"))
      (node (ref "R56") (pin "2") (pinfunction "2_2") (pintype "passive"))
      (node (ref "R63") (pin "1") (pinfunction "1_1") (pintype "passive"))
      (node (ref "R64") (pin "1") (pinfunction "1_1") (pintype "passive"))
      (node (ref "R65") (pin "1") (pinfunction "1_1") (pintype "passive"))
      (node (ref "R67") (pin "2") (pinfunction "2_2") (pintype "passive"))
      (node (ref "R7") (pin "2") (pinfunction "2_2") (pintype "passive"))
      (node (ref "R74") (pin "2") (pinfunction "2_2") (pintype "passive"))
      (node (ref "SV1") (pin "2") (pinfunction "2_2") (pintype "passive"))
      (node (ref "SV13") (pin "2") (pinfunction "2_2") (pintype "passive"))
      (node (ref "SV5") (pin "2") (pinfunction "2_2") (pintype "passive"))
      (node (ref "SV9") (pin "2") (pinfunction "2_2") (pintype "passive"))
      (node (ref "U13") (pin "2") (pinfunction "OUT_2") (pintype "output"))
      (node (ref "U13") (pin "4") (pinfunction "OUT_4") (pintype "output"))
      (node (ref "U19") (pin "2") (pinfunction "OUT_2") (pintype "output"))
      (node (ref "U19") (pin "4") (pinfunction "OUT_4") (pintype "output"))
      (node (ref "U2") (pin "2") (pinfunction "OUT_2") (pintype "output"))
      (node (ref "U2") (pin "4") (pinfunction "OUT_4") (pintype "output"))
      (node (ref "U7") (pin "2") (pinfunction "OUT_2") (pintype "output"))
      (node (ref "U7") (pin "4") (pinfunction "OUT_4") (pintype "output"))
    )
    (net (code "34") (name "GND") (class "Default")
      (node (ref "C1") (pin "2") (pinfunction "2_2") (pintype "passive"))
      (node (ref "C2") (pin "2") (pinfunction "2_2") (pintype "passive"))
      (node (ref "C21") (pin "2") (pinfunction "2_2") (pintype "passive"))
      (node (ref "C22") (pin "2") (pinfunction "2_2") (pintype "passive"))
      (node (ref "C23") (pin "2") (pinfunction "2_2") (pintype "passive"))
      (node (ref "C24") (pin "2") (pinfunction "2_2") (pintype "passive"))
      (node (ref "C26") (pin "2") (pinfunction "2_2") (pintype "passive"))
      (node (ref "C27") (pin "2") (pinfunction "2_2") (pintype "passive"))
      (node (ref "C28") (pin "2") (pinfunction "2_2") (pintype "passive"))
      (node (ref "C29") (pin "2") (pinfunction "2_2") (pintype "passive"))
      (node (ref "C3") (pin "2") (pinfunction "2_2") (pintype "passive"))
      (node (ref "C301") (pin "2") (pinfunction "2_2") (pintype "passive"))
      (node (ref "C302") (pin "2") (pinfunction "2_2") (pintype "passive"))
      (node (ref "C303") (pin "2") (pinfunction "2_2") (pintype "passive"))
      (node (ref "C304") (pin "2") (pinfunction "2_2") (pintype "passive"))
      (node (ref "C31") (pin "2") (pinfunction "2_2") (pintype "passive"))
      (node (ref "C4") (pin "2") (pinfunction "2_2") (pintype "passive"))
      (node (ref "C47") (pin "2") (pinfunction "2_2") (pintype "passive"))
      (node (ref "C48") (pin "2") (pinfunction "2_2") (pintype "passive"))
      (node (ref "C49") (pin "2") (pinfunction "2_2") (pintype "passive"))
      (node (ref "C5") (pin "2") (pinfunction "2_2") (pintype "passive"))
      (node (ref "C50") (pin "2") (pinfunction "2_2") (pintype "passive"))
      (node (ref "C52") (pin "2") (pinfunction "2_2") (pintype "passive"))
      (node (ref "C53") (pin "2") (pinfunction "2_2") (pintype "passive"))
      (node (ref "C54") (pin "2") (pinfunction "2_2") (pintype "passive"))
      (node (ref "C55") (pin "2") (pinfunction "2_2") (pintype "passive"))
      (node (ref "C57") (pin "2") (pinfunction "2_2") (pintype "passive"))
      (node (ref "C73") (pin "2") (pinfunction "2_2") (pintype "passive"))
      (node (ref "C74") (pin "2") (pinfunction "2_2") (pintype "passive"))
      (node (ref "C75") (pin "2") (pinfunction "2_2") (pintype "passive"))
      (node (ref "C76") (pin "2") (pinfunction "2_2") (pintype "passive"))
      (node (ref "C78") (pin "2") (pinfunction "2_2") (pintype "passive"))
      (node (ref "C79") (pin "2") (pinfunction "2_2") (pintype "passive"))
      (node (ref "C80") (pin "2") (pinfunction "2_2") (pintype "passive"))
      (node (ref "C81") (pin "2") (pinfunction "2_2") (pintype "passive"))
      (node (ref "C83") (pin "2") (pinfunction "2_2") (pintype "passive"))
      (node (ref "J2") (pin "A1_B12") (pinfunction "GND_A1_B12") (pintype "power_in"))
      (node (ref "J2") (pin "B1_A12") (pinfunction "GND_B1_A12") (pintype "power_in"))
      (node (ref "J2") (pin "S1") (pinfunction "SHELL_GND_S1") (pintype "power_in"))
      (node (ref "J2") (pin "S2") (pinfunction "SHELL_GND_S2") (pintype "power_in"))
      (node (ref "J2") (pin "S3") (pinfunction "SHELL_GND_S3") (pintype "power_in"))
      (node (ref "J2") (pin "S4") (pinfunction "SHELL_GND_S4") (pintype "power_in"))
      (node (ref "J4") (pin "A1_B12") (pinfunction "GND_A1_B12") (pintype "power_in"))
      (node (ref "J4") (pin "B1_A12") (pinfunction "GND_B1_A12") (pintype "power_in"))
      (node (ref "J4") (pin "S1") (pinfunction "SHELL_GND_S1") (pintype "power_in"))
      (node (ref "J4") (pin "S2") (pinfunction "SHELL_GND_S2") (pintype "power_in"))
      (node (ref "J4") (pin "S3") (pinfunction "SHELL_GND_S3") (pintype "power_in"))
      (node (ref "J4") (pin "S4") (pinfunction "SHELL_GND_S4") (pintype "power_in"))
      (node (ref "J5") (pin "A1_B12") (pinfunction "GND_A1_B12") (pintype "power_in"))
      (node (ref "J5") (pin "B1_A12") (pinfunction "GND_B1_A12") (pintype "power_in"))
      (node (ref "J5") (pin "S1") (pinfunction "SHELL_GND_S1") (pintype "power_in"))
      (node (ref "J5") (pin "S2") (pinfunction "SHELL_GND_S2") (pintype "power_in"))
      (node (ref "J5") (pin "S3") (pinfunction "SHELL_GND_S3") (pintype "power_in"))
      (node (ref "J5") (pin "S4") (pinfunction "SHELL_GND_S4") (pintype "power_in"))
      (node (ref "J7") (pin "A1_B12") (pinfunction "GND_A1_B12") (pintype "power_in"))
      (node (ref "J7") (pin "B1_A12") (pinfunction "GND_B1_A12") (pintype "power_in"))
      (node (ref "J7") (pin "S1") (pinfunction "SHELL_GND_S1") (pintype "power_in"))
      (node (ref "J7") (pin "S2") (pinfunction "SHELL_GND_S2") (pintype "power_in"))
      (node (ref "J7") (pin "S3") (pinfunction "SHELL_GND_S3") (pintype "power_in"))
      (node (ref "J7") (pin "S4") (pinfunction "SHELL_GND_S4") (pintype "power_in"))
      (node (ref "PWR") (pin "C") (pinfunction "C_C") (pintype "passive"))
      (node (ref "PWR2") (pin "C") (pinfunction "C_C") (pintype "passive"))
      (node (ref "PWR4") (pin "C") (pinfunction "C_C") (pintype "passive"))
      (node (ref "PWR6") (pin "C") (pinfunction "C_C") (pintype "passive"))
      (node (ref "Q15") (pin "2") (pinfunction "S_2") (pintype "bidirectional"))
      (node (ref "Q21") (pin "2") (pinfunction "S_2") (pintype "bidirectional"))
      (node (ref "Q3") (pin "2") (pinfunction "S_2") (pintype "bidirectional"))
      (node (ref "Q9") (pin "2") (pinfunction "S_2") (pintype "bidirectional"))
      (node (ref "R109") (pin "1") (pinfunction "1_1") (pintype "passive"))
      (node (ref "R111") (pin "1") (pinfunction "1_1") (pintype "passive"))
      (node (ref "R113") (pin "1") (pinfunction "1_1") (pintype "passive"))
      (node (ref "R115") (pin "1") (pinfunction "1_1") (pintype "passive"))
      (node (ref "R126") (pin "2") (pinfunction "2_2") (pintype "passive"))
      (node (ref "R135") (pin "2") (pinfunction "2_2") (pintype "passive"))
      (node (ref "R136") (pin "2") (pinfunction "2_2") (pintype "passive"))
      (node (ref "R15") (pin "2") (pinfunction "2_2") (pintype "passive"))
      (node (ref "R16") (pin "2") (pinfunction "2_2") (pintype "passive"))
      (node (ref "R169") (pin "1") (pinfunction "1_1") (pintype "passive"))
      (node (ref "R171") (pin "1") (pinfunction "1_1") (pintype "passive"))
      (node (ref "R173") (pin "1") (pinfunction "1_1") (pintype "passive"))
      (node (ref "R175") (pin "1") (pinfunction "1_1") (pintype "passive"))
      (node (ref "R186") (pin "2") (pinfunction "2_2") (pintype "passive"))
      (node (ref "R195") (pin "2") (pinfunction "2_2") (pintype "passive"))
      (node (ref "R196") (pin "2") (pinfunction "2_2") (pintype "passive"))
      (node (ref "R302") (pin "1") (pinfunction "1_1") (pintype "passive"))
      (node (ref "R304") (pin "1") (pinfunction "1_1") (pintype "passive"))
      (node (ref "R306") (pin "1") (pinfunction "1_1") (pintype "passive"))
      (node (ref "R308") (pin "1") (pinfunction "1_1") (pintype "passive"))
      (node (ref "R49") (pin "1") (pinfunction "1_1") (pintype "passive"))
      (node (ref "R51") (pin "1") (pinfunction "1_1") (pintype "passive"))
      (node (ref "R53") (pin "1") (pinfunction "1_1") (pintype "passive"))
      (node (ref "R55") (pin "1") (pinfunction "1_1") (pintype "passive"))
      (node (ref "R6") (pin "2") (pinfunction "2_2") (pintype "passive"))
      (node (ref "R66") (pin "2") (pinfunction "2_2") (pintype "passive"))
      (node (ref "R75") (pin "2") (pinfunction "2_2") (pintype "passive"))
      (node (ref "R76") (pin "2") (pinfunction "2_2") (pintype "passive"))
      (node (ref "SV1") (pin "1") (pinfunction "1_1") (pintype "passive"))
      (node (ref "SV10") (pin "1") (pinfunction "1_1") (pintype "passive"))
      (node (ref "SV13") (pin "1") (pinfunction "1_1") (pintype "passive"))
      (node (ref "SV14") (pin "1") (pinfunction "1_1") (pintype "passive"))
      (node (ref "SV2") (pin "1") (pinfunction "1_1") (pintype "passive"))
      (node (ref "SV5") (pin "1") (pinfunction "1_1") (pintype "passive"))
      (node (ref "SV6") (pin "1") (pinfunction "1_1") (pintype "passive"))
      (node (ref "SV9") (pin "1") (pinfunction "1_1") (pintype "passive"))
      (node (ref "U13") (pin "1") (pinfunction "ADJ_1") (pintype "input"))
      (node (ref "U14") (pin "19") (pinfunction "GND_1_19") (pintype "bidirectional"))
      (node (ref "U14") (pin "22") (pinfunction "GND_2_22") (pintype "bidirectional"))
      (node (ref "U14") (pin "25") (pinfunction "EP_25") (pintype "bidirectional"))
      (node (ref "U19") (pin "1") (pinfunction "ADJ_1") (pintype "input"))
      (node (ref "U2") (pin "1") (pinfunction "ADJ_1") (pintype "input"))
      (node (ref "U20") (pin "19") (pinfunction "GND_1_19") (pintype "bidirectional"))
      (node (ref "U20") (pin "22") (pinfunction "GND_2_22") (pintype "bidirectional"))
      (node (ref "U20") (pin "25") (pinfunction "EP_25") (pintype "bidirectional"))
      (node (ref "U3") (pin "19") (pinfunction "GND_1_19") (pintype "bidirectional"))
      (node (ref "U3") (pin "22") (pinfunction "GND_2_22") (pintype "bidirectional"))
      (node (ref "U3") (pin "25") (pinfunction "EP_25") (pintype "bidirectional"))
      (node (ref "U7") (pin "1") (pinfunction "ADJ_1") (pintype "input"))
      (node (ref "U8") (pin "19") (pinfunction "GND_1_19") (pintype "bidirectional"))
      (node (ref "U8") (pin "22") (pinfunction "GND_2_22") (pintype "bidirectional"))
      (node (ref "U8") (pin "25") (pinfunction "EP_25") (pintype "bidirectional"))
    )
    (net (code "35") (name "Net-(FAULT-PadC)") (class "Default")
      (node (ref "FAULT") (pin "C") (pinfunction "C_C") (pintype "passive"))
      (node (ref "R1") (pin "1") (pinfunction "1_1") (pintype "passive"))
    )
    (net (code "36") (name "Net-(FAULT2-PadC)") (class "Default")
      (node (ref "FAULT2") (pin "C") (pinfunction "C_C") (pintype "passive"))
      (node (ref "R62") (pin "1") (pinfunction "1_1") (pintype "passive"))
    )
    (net (code "37") (name "Net-(FAULT4-PadC)") (class "Default")
      (node (ref "FAULT4") (pin "C") (pinfunction "C_C") (pintype "passive"))
      (node (ref "R122") (pin "1") (pinfunction "1_1") (pintype "passive"))
    )
    (net (code "38") (name "Net-(FAULT6-PadC)") (class "Default")
      (node (ref "FAULT6") (pin "C") (pinfunction "C_C") (pintype "passive"))
      (node (ref "R182") (pin "1") (pinfunction "1_1") (pintype "passive"))
    )
    (net (code "39") (name "Net-(LED-PadA)") (class "Default")
      (node (ref "LED") (pin "A") (pinfunction "A_A") (pintype "passive"))
      (node (ref "R11") (pin "1") (pinfunction "1_1") (pintype "passive"))
    )
    (net (code "40") (name "Net-(LED2-PadA)") (class "Default")
      (node (ref "LED2") (pin "A") (pinfunction "A_A") (pintype "passive"))
      (node (ref "R69") (pin "1") (pinfunction "1_1") (pintype "passive"))
    )
    (net (code "41") (name "Net-(LED4-PadA)") (class "Default")
      (node (ref "LED4") (pin "A") (pinfunction "A_A") (pintype "passive"))
      (node (ref "R129") (pin "1") (pinfunction "1_1") (pintype "passive"))
    )
    (net (code "42") (name "Net-(LED6-PadA)") (class "Default")
      (node (ref "LED6") (pin "A") (pinfunction "A_A") (pintype "passive"))
      (node (ref "R189") (pin "1") (pinfunction "1_1") (pintype "passive"))
    )
    (net (code "43") (name "Net-(PWR-PadA)") (class "Default")
      (node (ref "PWR") (pin "A") (pinfunction "A_A") (pintype "passive"))
      (node (ref "R2") (pin "1") (pinfunction "1_1") (pintype "passive"))
    )
    (net (code "44") (name "Net-(PWR2-PadA)") (class "Default")
      (node (ref "PWR2") (pin "A") (pinfunction "A_A") (pintype "passive"))
      (node (ref "R48") (pin "1") (pinfunction "1_1") (pintype "passive"))
    )
    (net (code "45") (name "Net-(PWR4-PadA)") (class "Default")
      (node (ref "PWR4") (pin "A") (pinfunction "A_A") (pintype "passive"))
      (node (ref "R108") (pin "1") (pinfunction "1_1") (pintype "passive"))
    )
    (net (code "46") (name "Net-(PWR6-PadA)") (class "Default")
      (node (ref "PWR6") (pin "A") (pinfunction "A_A") (pintype "passive"))
      (node (ref "R168") (pin "1") (pinfunction "1_1") (pintype "passive"))
    )
    (net (code "47") (name "Net-(Q3-D)") (class "Default")
      (node (ref "Q3") (pin "3") (pinfunction "D_3") (pintype "bidirectional"))
      (node (ref "R1") (pin "2") (pinfunction "2_2") (pintype "passive"))
    )
    (net (code "48") (name "Net-(Q9-D)") (class "Default")
      (node (ref "Q9") (pin "3") (pinfunction "D_3") (pintype "bidirectional"))
      (node (ref "R62") (pin "2") (pinfunction "2_2") (pintype "passive"))
    )
    (net (code "49") (name "Net-(Q15-D)") (class "Default")
      (node (ref "Q15") (pin "3") (pinfunction "D_3") (pintype "bidirectional"))
      (node (ref "R122") (pin "2") (pinfunction "2_2") (pintype "passive"))
    )
    (net (code "50") (name "Net-(Q21-D)") (class "Default")
      (node (ref "Q21") (pin "3") (pinfunction "D_3") (pintype "bidirectional"))
      (node (ref "R182") (pin "2") (pinfunction "2_2") (pintype "passive"))
    )
    (net (code "51") (name "Net-(U3-HPI_INT)") (class "Default")
      (node (ref "R7") (pin "1") (pinfunction "1_1") (pintype "passive"))
      (node (ref "U3") (pin "7") (pinfunction "HPI_INT_7") (pintype "bidirectional"))
    )
    (net (code "52") (name "Net-(U3-ISNK_COARSE)") (class "Default")
      (node (ref "R305") (pin "1") (pinfunction "1_1") (pintype "passive"))
      (node (ref "R306") (pin "2") (pinfunction "2_2") (pintype "passive"))
      (node (ref "U3") (pin "5") (pinfunction "ISNK_COARSE_5") (pintype "bidirectional"))
    )
    (net (code "53") (name "Net-(U3-ISNK_FINE)") (class "Default")
      (node (ref "R307") (pin "1") (pinfunction "1_1") (pintype "passive"))
      (node (ref "R308") (pin "2") (pinfunction "2_2") (pintype "passive"))
      (node (ref "U3") (pin "6") (pinfunction "ISNK_FINE_6") (pintype "bidirectional"))
    )
    (net (code "54") (name "Net-(U3-VBUS_MAX)") (class "Default")
      (node (ref "R303") (pin "1") (pinfunction "1_1") (pintype "passive"))
      (node (ref "R304") (pin "2") (pinfunction "2_2") (pintype "passive"))
      (node (ref "U3") (pin "2") (pinfunction "VBUS_MAX_2") (pintype "bidirectional"))
    )
    (net (code "55") (name "Net-(U3-VBUS_MIN)") (class "Default")
      (node (ref "R301") (pin "1") (pinfunction "1_1") (pintype "passive"))
      (node (ref "R302") (pin "2") (pinfunction "2_2") (pintype "passive"))
      (node (ref "U3") (pin "1") (pinfunction "VBUS_MIN_1") (pintype "bidirectional"))
    )
    (net (code "56") (name "Net-(U8-HPI_INT)") (class "Default")
      (node (ref "R67") (pin "1") (pinfunction "1_1") (pintype "passive"))
      (node (ref "U8") (pin "7") (pinfunction "HPI_INT_7") (pintype "bidirectional"))
    )
    (net (code "57") (name "Net-(U8-ISNK_COARSE)") (class "Default")
      (node (ref "R53") (pin "2") (pinfunction "2_2") (pintype "passive"))
      (node (ref "R54") (pin "1") (pinfunction "1_1") (pintype "passive"))
      (node (ref "U8") (pin "5") (pinfunction "ISNK_COARSE_5") (pintype "bidirectional"))
    )
    (net (code "58") (name "Net-(U8-ISNK_FINE)") (class "Default")
      (node (ref "R55") (pin "2") (pinfunction "2_2") (pintype "passive"))
      (node (ref "R56") (pin "1") (pinfunction "1_1") (pintype "passive"))
      (node (ref "U8") (pin "6") (pinfunction "ISNK_FINE_6") (pintype "bidirectional"))
    )
    (net (code "59") (name "Net-(U8-VBUS_MAX)") (class "Default")
      (node (ref "R51") (pin "2") (pinfunction "2_2") (pintype "passive"))
      (node (ref "R52") (pin "1") (pinfunction "1_1") (pintype "passive"))
      (node (ref "U8") (pin "2") (pinfunction "VBUS_MAX_2") (pintype "bidirectional"))
    )
    (net (code "60") (name "Net-(U8-VBUS_MIN)") (class "Default")
      (node (ref "R49") (pin "2") (pinfunction "2_2") (pintype "passive"))
      (node (ref "R50") (pin "1") (pinfunction "1_1") (pintype "passive"))
      (node (ref "U8") (pin "1") (pinfunction "VBUS_MIN_1") (pintype "bidirectional"))
    )
    (net (code "61") (name "Net-(U14-HPI_INT)") (class "Default")
      (node (ref "R127") (pin "1") (pinfunction "1_1") (pintype "passive"))
      (node (ref "U14") (pin "7") (pinfunction "HPI_INT_7") (pintype "bidirectional"))
    )
    (net (code "62") (name "Net-(U14-ISNK_COARSE)") (class "Default")
      (node (ref "R113") (pin "2") (pinfunction "2_2") (pintype "passive"))
      (node (ref "R114") (pin "1") (pinfunction "1_1") (pintype "passive"))
      (node (ref "U14") (pin "5") (pinfunction "ISNK_COARSE_5") (pintype "bidirectional"))
    )
    (net (code "63") (name "Net-(U14-ISNK_FINE)") (class "Default")
      (node (ref "R115") (pin "2") (pinfunction "2_2") (pintype "passive"))
      (node (ref "R116") (pin "1") (pinfunction "1_1") (pintype "passive"))
      (node (ref "U14") (pin "6") (pinfunction "ISNK_FINE_6") (pintype "bidirectional"))
    )
    (net (code "64") (name "Net-(U14-VBUS_MAX)") (class "Default")
      (node (ref "R111") (pin "2") (pinfunction "2_2") (pintype "passive"))
      (node (ref "R112") (pin "1") (pinfunction "1_1") (pintype "passive"))
      (node (ref "U14") (pin "2") (pinfunction "VBUS_MAX_2") (pintype "bidirectional"))
    )
    (net (code "65") (name "Net-(U14-VBUS_MIN)") (class "Default")
      (node (ref "R109") (pin "2") (pinfunction "2_2") (pintype "passive"))
      (node (ref "R110") (pin "1") (pinfunction "1_1") (pintype "passive"))
      (node (ref "U14") (pin "1") (pinfunction "VBUS_MIN_1") (pintype "bidirectional"))
    )
    (net (code "66") (name "Net-(U20-HPI_INT)") (class "Default")
      (node (ref "R187") (pin "1") (pinfunction "1_1") (pintype "passive"))
      (node (ref "U20") (pin "7") (pinfunction "HPI_INT_7") (pintype "bidirectional"))
    )
    (net (code "67") (name "Net-(U20-ISNK_COARSE)") (class "Default")
      (node (ref "R173") (pin "2") (pinfunction "2_2") (pintype "passive"))
      (node (ref "R174") (pin "1") (pinfunction "1_1") (pintype "passive"))
      (node (ref "U20") (pin "5") (pinfunction "ISNK_COARSE_5") (pintype "bidirectional"))
    )
    (net (code "68") (name "Net-(U20-ISNK_FINE)") (class "Default")
      (node (ref "R175") (pin "2") (pinfunction "2_2") (pintype "passive"))
      (node (ref "R176") (pin "1") (pinfunction "1_1") (pintype "passive"))
      (node (ref "U20") (pin "6") (pinfunction "ISNK_FINE_6") (pintype "bidirectional"))
    )
    (net (code "69") (name "Net-(U20-VBUS_MAX)") (class "Default")
      (node (ref "R171") (pin "2") (pinfunction "2_2") (pintype "passive"))
      (node (ref "R172") (pin "1") (pinfunction "1_1") (pintype "passive"))
      (node (ref "U20") (pin "2") (pinfunction "VBUS_MAX_2") (pintype "bidirectional"))
    )
    (net (code "70") (name "Net-(U20-VBUS_MIN)") (class "Default")
      (node (ref "R169") (pin "2") (pinfunction "2_2") (pintype "passive"))
      (node (ref "R170") (pin "1") (pinfunction "1_1") (pintype "passive"))
      (node (ref "U20") (pin "1") (pinfunction "VBUS_MIN_1") (pintype "bidirectional"))
    )
    (net (code "71") (name "RESET") (class "Default")
      (node (ref "JTAG") (pin "10") (pinfunction "~{RESET}_10") (pintype "bidirectional"))
      (node (ref "JTAG2") (pin "10") (pinfunction "~{RESET}_10") (pintype "bidirectional"))
      (node (ref "JTAG4") (pin "10") (pinfunction "~{RESET}_10") (pintype "bidirectional"))
      (node (ref "JTAG6") (pin "10") (pinfunction "~{RESET}_10") (pintype "bidirectional"))
      (node (ref "R128") (pin "1") (pinfunction "1_1") (pintype "passive"))
      (node (ref "R188") (pin "1") (pinfunction "1_1") (pintype "passive"))
      (node (ref "R68") (pin "1") (pinfunction "1_1") (pintype "passive"))
      (node (ref "R8") (pin "1") (pinfunction "1_1") (pintype "passive"))
      (node (ref "RESET") (pin "1") (pinfunction "1_1") (pintype "passive"))
      (node (ref "RESET2") (pin "1") (pinfunction "1_1") (pintype "passive"))
      (node (ref "RESET4") (pin "1") (pinfunction "1_1") (pintype "passive"))
      (node (ref "RESET6") (pin "1") (pinfunction "1_1") (pintype "passive"))
      (node (ref "U1") (pin "26") (pinfunction "~{RESET}_26") (pintype "passive"))
      (node (ref "U15") (pin "26") (pinfunction "~{RESET}_26") (pintype "passive"))
      (node (ref "U21") (pin "26") (pinfunction "~{RESET}_26") (pintype "passive"))
      (node (ref "U9") (pin "26") (pinfunction "~{RESET}_26") (pintype "passive"))
    )
    (net (code "72") (name "SCL") (class "Default")
      (node (ref "R12") (pin "2") (pinfunction "2_2") (pintype "passive"))
      (node (ref "R125") (pin "2") (pinfunction "2_2") (pintype "passive"))
      (node (ref "R132") (pin "2") (pinfunction "2_2") (pintype "passive"))
      (node (ref "R185") (pin "2") (pinfunction "2_2") (pintype "passive"))
      (node (ref "R192") (pin "2") (pinfunction "2_2") (pintype "passive"))
      (node (ref "R5") (pin "2") (pinfunction "2_2") (pintype "passive"))
      (node (ref "R65") (pin "2") (pinfunction "2_2") (pintype "passive"))
      (node (ref "R72") (pin "2") (pinfunction "2_2") (pintype "passive"))
      (node (ref "U14") (pin "13") (pinfunction "HPI_SCL_13") (pintype "bidirectional"))
      (node (ref "U20") (pin "13") (pinfunction "HPI_SCL_13") (pintype "bidirectional"))
      (node (ref "U3") (pin "13") (pinfunction "HPI_SCL_13") (pintype "bidirectional"))
      (node (ref "U8") (pin "13") (pinfunction "HPI_SCL_13") (pintype "bidirectional"))
    )
    (net (code "73") (name "SDA") (class "Default")
      (node (ref "R124") (pin "2") (pinfunction "2_2") (pintype "passive"))
      (node (ref "R13") (pin "2") (pinfunction "2_2") (pintype "passive"))
      (node (ref "R133") (pin "2") (pinfunction "2_2") (pintype "passive"))
      (node (ref "R184") (pin "2") (pinfunction "2_2") (pintype "passive"))
      (node (ref "R193") (pin "2") (pinfunction "2_2") (pintype "passive"))
      (node (ref "R4") (pin "2") (pinfunction "2_2") (pintype "passive"))
      (node (ref "R64") (pin "2") (pinfunction "2_2") (pintype "passive"))
      (node (ref "R73") (pin "2") (pinfunction "2_2") (pintype "passive"))
      (node (ref "U14") (pin "12") (pinfunction "HPI_SDA_12") (pintype "bidirectional"))
      (node (ref "U20") (pin "12") (pinfunction "HPI_SDA_12") (pintype "bidirectional"))
      (node (ref "U3") (pin "12") (pinfunction "HPI_SDA_12") (pintype "bidirectional"))
      (node (ref "U8") (pin "12") (pinfunction "HPI_SDA_12") (pintype "bidirectional"))
    )
    (net (code "74") (name "SWCLK") (class "Default")
      (node (ref "JTAG") (pin "4") (pinfunction "SWDCLK/TCK_4") (pintype "bidirectional"))
      (node (ref "JTAG2") (pin "4") (pinfunction "SWDCLK/TCK_4") (pintype "bidirectional"))
      (node (ref "JTAG4") (pin "4") (pinfunction "SWDCLK/TCK_4") (pintype "bidirectional"))
      (node (ref "JTAG6") (pin "4") (pinfunction "SWDCLK/TCK_4") (pintype "bidirectional"))
      (node (ref "R137") (pin "1") (pinfunction "1_1") (pintype "passive"))
      (node (ref "R17") (pin "1") (pinfunction "1_1") (pintype "passive"))
      (node (ref "R197") (pin "1") (pinfunction "1_1") (pintype "passive"))
      (node (ref "R77") (pin "1") (pinfunction "1_1") (pintype "passive"))
      (node (ref "U1") (pin "31") (pinfunction "PA30_31") (pintype "bidirectional"))
      (node (ref "U15") (pin "31") (pinfunction "PA30_31") (pintype "bidirectional"))
      (node (ref "U21") (pin "31") (pinfunction "PA30_31") (pintype "bidirectional"))
      (node (ref "U9") (pin "31") (pinfunction "PA30_31") (pintype "bidirectional"))
    )
    (net (code "75") (name "SWDIO") (class "Default")
      (node (ref "JTAG") (pin "2") (pinfunction "SWDIO/TMS_2") (pintype "bidirectional"))
      (node (ref "JTAG2") (pin "2") (pinfunction "SWDIO/TMS_2") (pintype "bidirectional"))
      (node (ref "JTAG4") (pin "2") (pinfunction "SWDIO/TMS_2") (pintype "bidirectional"))
      (node (ref "JTAG6") (pin "2") (pinfunction "SWDIO/TMS_2") (pintype "bidirectional"))
      (node (ref "U1") (pin "32") (pinfunction "PA31_32") (pintype "bidirectional"))
      (node (ref "U15") (pin "32") (pinfunction "PA31_32") (pintype "bidirectional"))
      (node (ref "U21") (pin "32") (pinfunction "PA31_32") (pintype "bidirectional"))
      (node (ref "U9") (pin "32") (pinfunction "PA31_32") (pintype "bidirectional"))
    )
    (net (code "76") (name "USB_D_N") (class "Default")
      (node (ref "J2") (pin "A7") (pinfunction "DN1_A7") (pintype "bidirectional"))
      (node (ref "J2") (pin "B7") (pinfunction "DN2_B7") (pintype "bidirectional"))
      (node (ref "J4") (pin "A7") (pinfunction "DN1_A7") (pintype "bidirectional"))
      (node (ref "J4") (pin "B7") (pinfunction "DN2_B7") (pintype "bidirectional"))
      (node (ref "J5") (pin "A7") (pinfunction "DN1_A7") (pintype "bidirectional"))
      (node (ref "J5") (pin "B7") (pinfunction "DN2_B7") (pintype "bidirectional"))
      (node (ref "J7") (pin "A7") (pinfunction "DN1_A7") (pintype "bidirectional"))
      (node (ref "J7") (pin "B7") (pinfunction "DN2_B7") (pintype "bidirectional"))
      (node (ref "R130") (pin "1") (pinfunction "1_1") (pintype "passive"))
      (node (ref "R190") (pin "1") (pinfunction "1_1") (pintype "passive"))
      (node (ref "R70") (pin "1") (pinfunction "1_1") (pintype "passive"))
      (node (ref "R9") (pin "1") (pinfunction "1_1") (pintype "passive"))
    )
    (net (code "77") (name "USB_D_P") (class "Default")
      (node (ref "J2") (pin "A6") (pinfunction "DP1_A6") (pintype "bidirectional"))
      (node (ref "J2") (pin "B6") (pinfunction "DP2_B6") (pintype "bidirectional"))
      (node (ref "J4") (pin "A6") (pinfunction "DP1_A6") (pintype "bidirectional"))
      (node (ref "J4") (pin "B6") (pinfunction "DP2_B6") (pintype "bidirectional"))
      (node (ref "J5") (pin "A6") (pinfunction "DP1_A6") (pintype "bidirectional"))
      (node (ref "J5") (pin "B6") (pinfunction "DP2_B6") (pintype "bidirectional"))
      (node (ref "J7") (pin "A6") (pinfunction "DP1_A6") (pintype "bidirectional"))
      (node (ref "J7") (pin "B6") (pinfunction "DP2_B6") (pintype "bidirectional"))
      (node (ref "R10") (pin "1") (pinfunction "1_1") (pintype "passive"))
      (node (ref "R131") (pin "1") (pinfunction "1_1") (pintype "passive"))
      (node (ref "R191") (pin "1") (pinfunction "1_1") (pintype "passive"))
      (node (ref "R71") (pin "1") (pinfunction "1_1") (pintype "passive"))
    )
    (net (code "78") (name "_3V3") (class "Default")
      (node (ref "C10") (pin "1") (pinfunction "1_1") (pintype "passive"))
      (node (ref "C33") (pin "1") (pinfunction "1_1") (pintype "passive"))
      (node (ref "C59") (pin "1") (pinfunction "1_1") (pintype "passive"))
      (node (ref "C85") (pin "1") (pinfunction "1_1") (pintype "passive"))
      (node (ref "JTAG") (pin "1") (pinfunction "VCC_1") (pintype "bidirectional"))
      (node (ref "JTAG2") (pin "1") (pinfunction "VCC_1") (pintype "bidirectional"))
      (node (ref "JTAG4") (pin "1") (pinfunction "VCC_1") (pintype "bidirectional"))
      (node (ref "JTAG6") (pin "1") (pinfunction "VCC_1") (pintype "bidirectional"))
      (node (ref "R128") (pin "2") (pinfunction "2_2") (pintype "passive"))
      (node (ref "R134") (pin "1") (pinfunction "1_1") (pintype "passive"))
      (node (ref "R137") (pin "2") (pinfunction "2_2") (pintype "passive"))
      (node (ref "R14") (pin "1") (pinfunction "1_1") (pintype "passive"))
      (node (ref "R17") (pin "2") (pinfunction "2_2") (pintype "passive"))
      (node (ref "R188") (pin "2") (pinfunction "2_2") (pintype "passive"))
      (node (ref "R194") (pin "1") (pinfunction "1_1") (pintype "passive"))
      (node (ref "R197") (pin "2") (pinfunction "2_2") (pintype "passive"))
      (node (ref "R68") (pin "2") (pinfunction "2_2") (pintype "passive"))
      (node (ref "R74") (pin "1") (pinfunction "1_1") (pintype "passive"))
      (node (ref "R77") (pin "2") (pinfunction "2_2") (pintype "passive"))
      (node (ref "R8") (pin "2") (pinfunction "2_2") (pintype "passive"))
      (node (ref "U1") (pin "30") (pinfunction "VDDIN_30") (pintype "power_in"))
      (node (ref "U1") (pin "9") (pinfunction "VDDANA_9") (pintype "power_in"))
      (node (ref "U15") (pin "30") (pinfunction "VDDIN_30") (pintype "power_in"))
      (node (ref "U15") (pin "9") (pinfunction "VDDANA_9") (pintype "power_in"))
      (node (ref "U21") (pin "30") (pinfunction "VDDIN_30") (pintype "power_in"))
      (node (ref "U21") (pin "9") (pinfunction "VDDANA_9") (pintype "power_in"))
      (node (ref "U9") (pin "30") (pinfunction "VDDIN_30") (pintype "power_in"))
      (node (ref "U9") (pin "9") (pinfunction "VDDANA_9") (pintype "power_in"))
    )
    (net (code "79") (name "_GND") (class "Default")
      (node (ref "C10") (pin "2") (pinfunction "2_2") (pintype "passive"))
      (node (ref "C32") (pin "2") (pinfunction "2_2") (pintype "passive"))
      (node (ref "C33") (pin "2") (pinfunction "2_2") (pintype "passive"))
      (node (ref "C58") (pin "2") (pinfunction "2_2") (pintype "passive"))
      (node (ref "C59") (pin "2") (pinfunction "2_2") (pintype "passive"))
      (node (ref "C6") (pin "2") (pinfunction "2_2") (pintype "passive"))
      (node (ref "C84") (pin "2") (pinfunction "2_2") (pintype "passive"))
      (node (ref "C85") (pin "2") (pinfunction "2_2") (pintype "passive"))
      (node (ref "JTAG") (pin "3") (pinfunction "GND_3") (pintype "bidirectional"))
      (node (ref "JTAG") (pin "5") (pinfunction "GND_5") (pintype "bidirectional"))
      (node (ref "JTAG2") (pin "3") (pinfunction "GND_3") (pintype "bidirectional"))
      (node (ref "JTAG2") (pin "5") (pinfunction "GND_5") (pintype "bidirectional"))
      (node (ref "JTAG4") (pin "3") (pinfunction "GND_3") (pintype "bidirectional"))
      (node (ref "JTAG4") (pin "5") (pinfunction "GND_5") (pintype "bidirectional"))
      (node (ref "JTAG6") (pin "3") (pinfunction "GND_3") (pintype "bidirectional"))
      (node (ref "JTAG6") (pin "5") (pinfunction "GND_5") (pintype "bidirectional"))
      (node (ref "LED") (pin "C") (pinfunction "C_C") (pintype "passive"))
      (node (ref "LED2") (pin "C") (pinfunction "C_C") (pintype "passive"))
      (node (ref "LED4") (pin "C") (pinfunction "C_C") (pintype "passive"))
      (node (ref "LED6") (pin "C") (pinfunction "C_C") (pintype "passive"))
      (node (ref "R135") (pin "1") (pinfunction "1_1") (pintype "passive"))
      (node (ref "R136") (pin "1") (pinfunction "1_1") (pintype "passive"))
      (node (ref "R15") (pin "1") (pinfunction "1_1") (pintype "passive"))
      (node (ref "R16") (pin "1") (pinfunction "1_1") (pintype "passive"))
      (node (ref "R195") (pin "1") (pinfunction "1_1") (pintype "passive"))
      (node (ref "R196") (pin "1") (pinfunction "1_1") (pintype "passive"))
      (node (ref "R75") (pin "1") (pinfunction "1_1") (pintype "passive"))
      (node (ref "R76") (pin "1") (pinfunction "1_1") (pintype "passive"))
      (node (ref "RESET") (pin "2") (pinfunction "2_2") (pintype "passive"))
      (node (ref "RESET2") (pin "2") (pinfunction "2_2") (pintype "passive"))
      (node (ref "RESET4") (pin "2") (pinfunction "2_2") (pintype "passive"))
      (node (ref "RESET6") (pin "2") (pinfunction "2_2") (pintype "passive"))
      (node (ref "U1") (pin "10") (pinfunction "GND_2_10") (pintype "passive"))
      (node (ref "U1") (pin "28") (pinfunction "GND_28") (pintype "passive"))
      (node (ref "U15") (pin "10") (pinfunction "GND_2_10") (pintype "passive"))
      (node (ref "U15") (pin "28") (pinfunction "GND_28") (pintype "passive"))
      (node (ref "U21") (pin "10") (pinfunction "GND_2_10") (pintype "passive"))
      (node (ref "U21") (pin "28") (pinfunction "GND_28") (pintype "passive"))
      (node (ref "U9") (pin "10") (pinfunction "GND_2_10") (pintype "passive"))
      (node (ref "U9") (pin "28") (pinfunction "GND_28") (pintype "passive"))
    )
    (net (code "80") (name "unconnected-(J2-SBU1-PadA8)") (class "Default")
      (node (ref "J2") (pin "A8") (pinfunction "SBU1_A8") (pintype "bidirectional"))
    )
    (net (code "81") (name "unconnected-(J2-SBU2-PadB8)") (class "Default")
      (node (ref "J2") (pin "B8") (pinfunction "SBU2_B8") (pintype "bidirectional"))
    )
    (net (code "82") (name "unconnected-(J4-SBU1-PadA8)") (class "Default")
      (node (ref "J4") (pin "A8") (pinfunction "SBU1_A8") (pintype "bidirectional"))
    )
    (net (code "83") (name "unconnected-(J4-SBU2-PadB8)") (class "Default")
      (node (ref "J4") (pin "B8") (pinfunction "SBU2_B8") (pintype "bidirectional"))
    )
    (net (code "84") (name "unconnected-(J5-SBU1-PadA8)") (class "Default")
      (node (ref "J5") (pin "A8") (pinfunction "SBU1_A8") (pintype "bidirectional"))
    )
    (net (code "85") (name "unconnected-(J5-SBU2-PadB8)") (class "Default")
      (node (ref "J5") (pin "B8") (pinfunction "SBU2_B8") (pintype "bidirectional"))
    )
    (net (code "86") (name "unconnected-(J7-SBU1-PadA8)") (class "Default")
      (node (ref "J7") (pin "A8") (pinfunction "SBU1_A8") (pintype "bidirectional"))
    )
    (net (code "87") (name "unconnected-(J7-SBU2-PadB8)") (class "Default")
      (node (ref "J7") (pin "B8") (pinfunction "SBU2_B8") (pintype "bidirectional"))
    )
    (net (code "88") (name "unconnected-(JTAG-NC{slash}TDI-Pad8)") (class "Default")
      (node (ref "JTAG") (pin "8") (pinfunction "NC/TDI_8") (pintype "bidirectional"))
    )
    (net (code "89") (name "unconnected-(JTAG2-NC{slash}TDI-Pad8)") (class "Default")
      (node (ref "JTAG2") (pin "8") (pinfunction "NC/TDI_8") (pintype "bidirectional"))
    )
    (net (code "90") (name "unconnected-(JTAG4-NC{slash}TDI-Pad8)") (class "Default")
      (node (ref "JTAG4") (pin "8") (pinfunction "NC/TDI_8") (pintype "bidirectional"))
    )
    (net (code "91") (name "unconnected-(JTAG6-NC{slash}TDI-Pad8)") (class "Default")
      (node (ref "JTAG6") (pin "8") (pinfunction "NC/TDI_8") (pintype "bidirectional"))
    )
    (net (code "92") (name "unconnected-(U1-PA00-Pad1)") (class "Default")
      (node (ref "U1") (pin "1") (pinfunction "PA00_1") (pintype "bidirectional"))
    )
    (net (code "93") (name "unconnected-(U1-PA01-Pad2)") (class "Default")
      (node (ref "U1") (pin "2") (pinfunction "PA01_2") (pintype "bidirectional"))
    )
    (net (code "94") (name "unconnected-(U1-PA02-Pad3)") (class "Default")
      (node (ref "U1") (pin "3") (pinfunction "PA02_3") (pintype "bidirectional"))
    )
    (net (code "95") (name "unconnected-(U1-PA03-Pad4)") (class "Default")
      (node (ref "U1") (pin "4") (pinfunction "PA03_4") (pintype "bidirectional"))
    )
    (net (code "96") (name "unconnected-(U1-PA04-Pad5)") (class "Default")
      (node (ref "U1") (pin "5") (pinfunction "PA04_5") (pintype "bidirectional"))
    )
    (net (code "97") (name "unconnected-(U1-PA05-Pad6)") (class "Default")
      (node (ref "U1") (pin "6") (pinfunction "PA05_6") (pintype "bidirectional"))
    )
    (net (code "98") (name "unconnected-(U1-PA06-Pad7)") (class "Default")
      (node (ref "U1") (pin "7") (pinfunction "PA06_7") (pintype "bidirectional"))
    )
    (net (code "99") (name "unconnected-(U1-PA10-Pad13)") (class "Default")
      (node (ref "U1") (pin "13") (pinfunction "PA10_13") (pintype "bidirectional"))
    )
    (net (code "100") (name "unconnected-(U1-PA27-Pad25)") (class "Default")
      (node (ref "U1") (pin "25") (pinfunction "PA27_25") (pintype "bidirectional"))
    )
    (net (code "101") (name "unconnected-(U1-PA28-Pad27)") (class "Default")
      (node (ref "U1") (pin "27") (pinfunction "PA28_27") (pintype "bidirectional"))
    )
    (net (code "102") (name "unconnected-(U3-D+-Pad17)") (class "Default")
      (node (ref "U3") (pin "17") (pinfunction "D+_17") (pintype "bidirectional"))
    )
    (net (code "103") (name "unconnected-(U3-D--Pad16)") (class "Default")
      (node (ref "U3") (pin "16") (pinfunction "D-_16") (pintype "bidirectional"))
    )
    (net (code "104") (name "unconnected-(U3-DNU1-Pad20)") (class "Default")
      (node (ref "U3") (pin "20") (pinfunction "DNU1_20") (pintype "bidirectional"))
    )
    (net (code "105") (name "unconnected-(U3-DNU2-Pad21)") (class "Default")
      (node (ref "U3") (pin "21") (pinfunction "DNU2_21") (pintype "bidirectional"))
    )
    (net (code "106") (name "unconnected-(U3-GPIO_1-Pad8)") (class "Default")
      (node (ref "U3") (pin "8") (pinfunction "GPIO_1_8") (pintype "bidirectional"))
    )
    (net (code "107") (name "unconnected-(U8-D+-Pad17)") (class "Default")
      (node (ref "U8") (pin "17") (pinfunction "D+_17") (pintype "bidirectional"))
    )
    (net (code "108") (name "unconnected-(U8-D--Pad16)") (class "Default")
      (node (ref "U8") (pin "16") (pinfunction "D-_16") (pintype "bidirectional"))
    )
    (net (code "109") (name "unconnected-(U8-DNU1-Pad20)") (class "Default")
      (node (ref "U8") (pin "20") (pinfunction "DNU1_20") (pintype "bidirectional"))
    )
    (net (code "110") (name "unconnected-(U8-DNU2-Pad21)") (class "Default")
      (node (ref "U8") (pin "21") (pinfunction "DNU2_21") (pintype "bidirectional"))
    )
    (net (code "111") (name "unconnected-(U8-GPIO_1-Pad8)") (class "Default")
      (node (ref "U8") (pin "8") (pinfunction "GPIO_1_8") (pintype "bidirectional"))
    )
    (net (code "112") (name "unconnected-(U9-PA00-Pad1)") (class "Default")
      (node (ref "U9") (pin "1") (pinfunction "PA00_1") (pintype "bidirectional"))
    )
    (net (code "113") (name "unconnected-(U9-PA01-Pad2)") (class "Default")
      (node (ref "U9") (pin "2") (pinfunction "PA01_2") (pintype "bidirectional"))
    )
    (net (code "114") (name "unconnected-(U9-PA02-Pad3)") (class "Default")
      (node (ref "U9") (pin "3") (pinfunction "PA02_3") (pintype "bidirectional"))
    )
    (net (code "115") (name "unconnected-(U9-PA03-Pad4)") (class "Default")
      (node (ref "U9") (pin "4") (pinfunction "PA03_4") (pintype "bidirectional"))
    )
    (net (code "116") (name "unconnected-(U9-PA04-Pad5)") (class "Default")
      (node (ref "U9") (pin "5") (pinfunction "PA04_5") (pintype "bidirectional"))
    )
    (net (code "117") (name "unconnected-(U9-PA05-Pad6)") (class "Default")
      (node (ref "U9") (pin "6") (pinfunction "PA05_6") (pintype "bidirectional"))
    )
    (net (code "118") (name "unconnected-(U9-PA06-Pad7)") (class "Default")
      (node (ref "U9") (pin "7") (pinfunction "PA06_7") (pintype "bidirectional"))
    )
    (net (code "119") (name "unconnected-(U9-PA10-Pad13)") (class "Default")
      (node (ref "U9") (pin "13") (pinfunction "PA10_13") (pintype "bidirectional"))
    )
    (net (code "120") (name "unconnected-(U9-PA27-Pad25)") (class "Default")
      (node (ref "U9") (pin "25") (pinfunction "PA27_25") (pintype "bidirectional"))
    )
    (net (code "121") (name "unconnected-(U9-PA28-Pad27)") (class "Default")
      (node (ref "U9") (pin "27") (pinfunction "PA28_27") (pintype "bidirectional"))
    )
    (net (code "122") (name "unconnected-(U14-D+-Pad17)") (class "Default")
      (node (ref "U14") (pin "17") (pinfunction "D+_17") (pintype "bidirectional"))
    )
    (net (code "123") (name "unconnected-(U14-D--Pad16)") (class "Default")
      (node (ref "U14") (pin "16") (pinfunction "D-_16") (pintype "bidirectional"))
    )
    (net (code "124") (name "unconnected-(U14-DNU1-Pad20)") (class "Default")
      (node (ref "U14") (pin "20") (pinfunction "DNU1_20") (pintype "bidirectional"))
    )
    (net (code "125") (name "unconnected-(U14-DNU2-Pad21)") (class "Default")
      (node (ref "U14") (pin "21") (pinfunction "DNU2_21") (pintype "bidirectional"))
    )
    (net (code "126") (name "unconnected-(U14-GPIO_1-Pad8)") (class "Default")
      (node (ref "U14") (pin "8") (pinfunction "GPIO_1_8") (pintype "bidirectional"))
    )
    (net (code "127") (name "unconnected-(U15-PA00-Pad1)") (class "Default")
      (node (ref "U15") (pin "1") (pinfunction "PA00_1") (pintype "bidirectional"))
    )
    (net (code "128") (name "unconnected-(U15-PA01-Pad2)") (class "Default")
      (node (ref "U15") (pin "2") (pinfunction "PA01_2") (pintype "bidirectional"))
    )
    (net (code "129") (name "unconnected-(U15-PA02-Pad3)") (class "Default")
      (node (ref "U15") (pin "3") (pinfunction "PA02_3") (pintype "bidirectional"))
    )
    (net (code "130") (name "unconnected-(U15-PA03-Pad4)") (class "Default")
      (node (ref "U15") (pin "4") (pinfunction "PA03_4") (pintype "bidirectional"))
    )
    (net (code "131") (name "unconnected-(U15-PA04-Pad5)") (class "Default")
      (node (ref "U15") (pin "5") (pinfunction "PA04_5") (pintype "bidirectional"))
    )
    (net (code "132") (name "unconnected-(U15-PA05-Pad6)") (class "Default")
      (node (ref "U15") (pin "6") (pinfunction "PA05_6") (pintype "bidirectional"))
    )
    (net (code "133") (name "unconnected-(U15-PA06-Pad7)") (class "Default")
      (node (ref "U15") (pin "7") (pinfunction "PA06_7") (pintype "bidirectional"))
    )
    (net (code "134") (name "unconnected-(U15-PA10-Pad13)") (class "Default")
      (node (ref "U15") (pin "13") (pinfunction "PA10_13") (pintype "bidirectional"))
    )
    (net (code "135") (name "unconnected-(U15-PA27-Pad25)") (class "Default")
      (node (ref "U15") (pin "25") (pinfunction "PA27_25") (pintype "bidirectional"))
    )
    (net (code "136") (name "unconnected-(U15-PA28-Pad27)") (class "Default")
      (node (ref "U15") (pin "27") (pinfunction "PA28_27") (pintype "bidirectional"))
    )
    (net (code "137") (name "unconnected-(U20-D+-Pad17)") (class "Default")
      (node (ref "U20") (pin "17") (pinfunction "D+_17") (pintype "bidirectional"))
    )
    (net (code "138") (name "unconnected-(U20-D--Pad16)") (class "Default")
      (node (ref "U20") (pin "16") (pinfunction "D-_16") (pintype "bidirectional"))
    )
    (net (code "139") (name "unconnected-(U20-DNU1-Pad20)") (class "Default")
      (node (ref "U20") (pin "20") (pinfunction "DNU1_20") (pintype "bidirectional"))
    )
    (net (code "140") (name "unconnected-(U20-DNU2-Pad21)") (class "Default")
      (node (ref "U20") (pin "21") (pinfunction "DNU2_21") (pintype "bidirectional"))
    )
    (net (code "141") (name "unconnected-(U20-GPIO_1-Pad8)") (class "Default")
      (node (ref "U20") (pin "8") (pinfunction "GPIO_1_8") (pintype "bidirectional"))
    )
    (net (code "142") (name "unconnected-(U21-PA00-Pad1)") (class "Default")
      (node (ref "U21") (pin "1") (pinfunction "PA00_1") (pintype "bidirectional"))
    )
    (net (code "143") (name "unconnected-(U21-PA01-Pad2)") (class "Default")
      (node (ref "U21") (pin "2") (pinfunction "PA01_2") (pintype "bidirectional"))
    )
    (net (code "144") (name "unconnected-(U21-PA02-Pad3)") (class "Default")
      (node (ref "U21") (pin "3") (pinfunction "PA02_3") (pintype "bidirectional"))
    )
    (net (code "145") (name "unconnected-(U21-PA03-Pad4)") (class "Default")
      (node (ref "U21") (pin "4") (pinfunction "PA03_4") (pintype "bidirectional"))
    )
    (net (code "146") (name "unconnected-(U21-PA04-Pad5)") (class "Default")
      (node (ref "U21") (pin "5") (pinfunction "PA04_5") (pintype "bidirectional"))
    )
    (net (code "147") (name "unconnected-(U21-PA05-Pad6)") (class "Default")
      (node (ref "U21") (pin "6") (pinfunction "PA05_6") (pintype "bidirectional"))
    )
    (net (code "148") (name "unconnected-(U21-PA06-Pad7)") (class "Default")
      (node (ref "U21") (pin "7") (pinfunction "PA06_7") (pintype "bidirectional"))
    )
    (net (code "149") (name "unconnected-(U21-PA10-Pad13)") (class "Default")
      (node (ref "U21") (pin "13") (pinfunction "PA10_13") (pintype "bidirectional"))
    )
    (net (code "150") (name "unconnected-(U21-PA27-Pad25)") (class "Default")
      (node (ref "U21") (pin "25") (pinfunction "PA27_25") (pintype "bidirectional"))
    )
    (net (code "151") (name "unconnected-(U21-PA28-Pad27)") (class "Default")
      (node (ref "U21") (pin "27") (pinfunction "PA28_27") (pintype "bidirectional"))
    )
  )
)
